# BMS_25.net
KiCad netlist of a schematic drawn in EAGLE
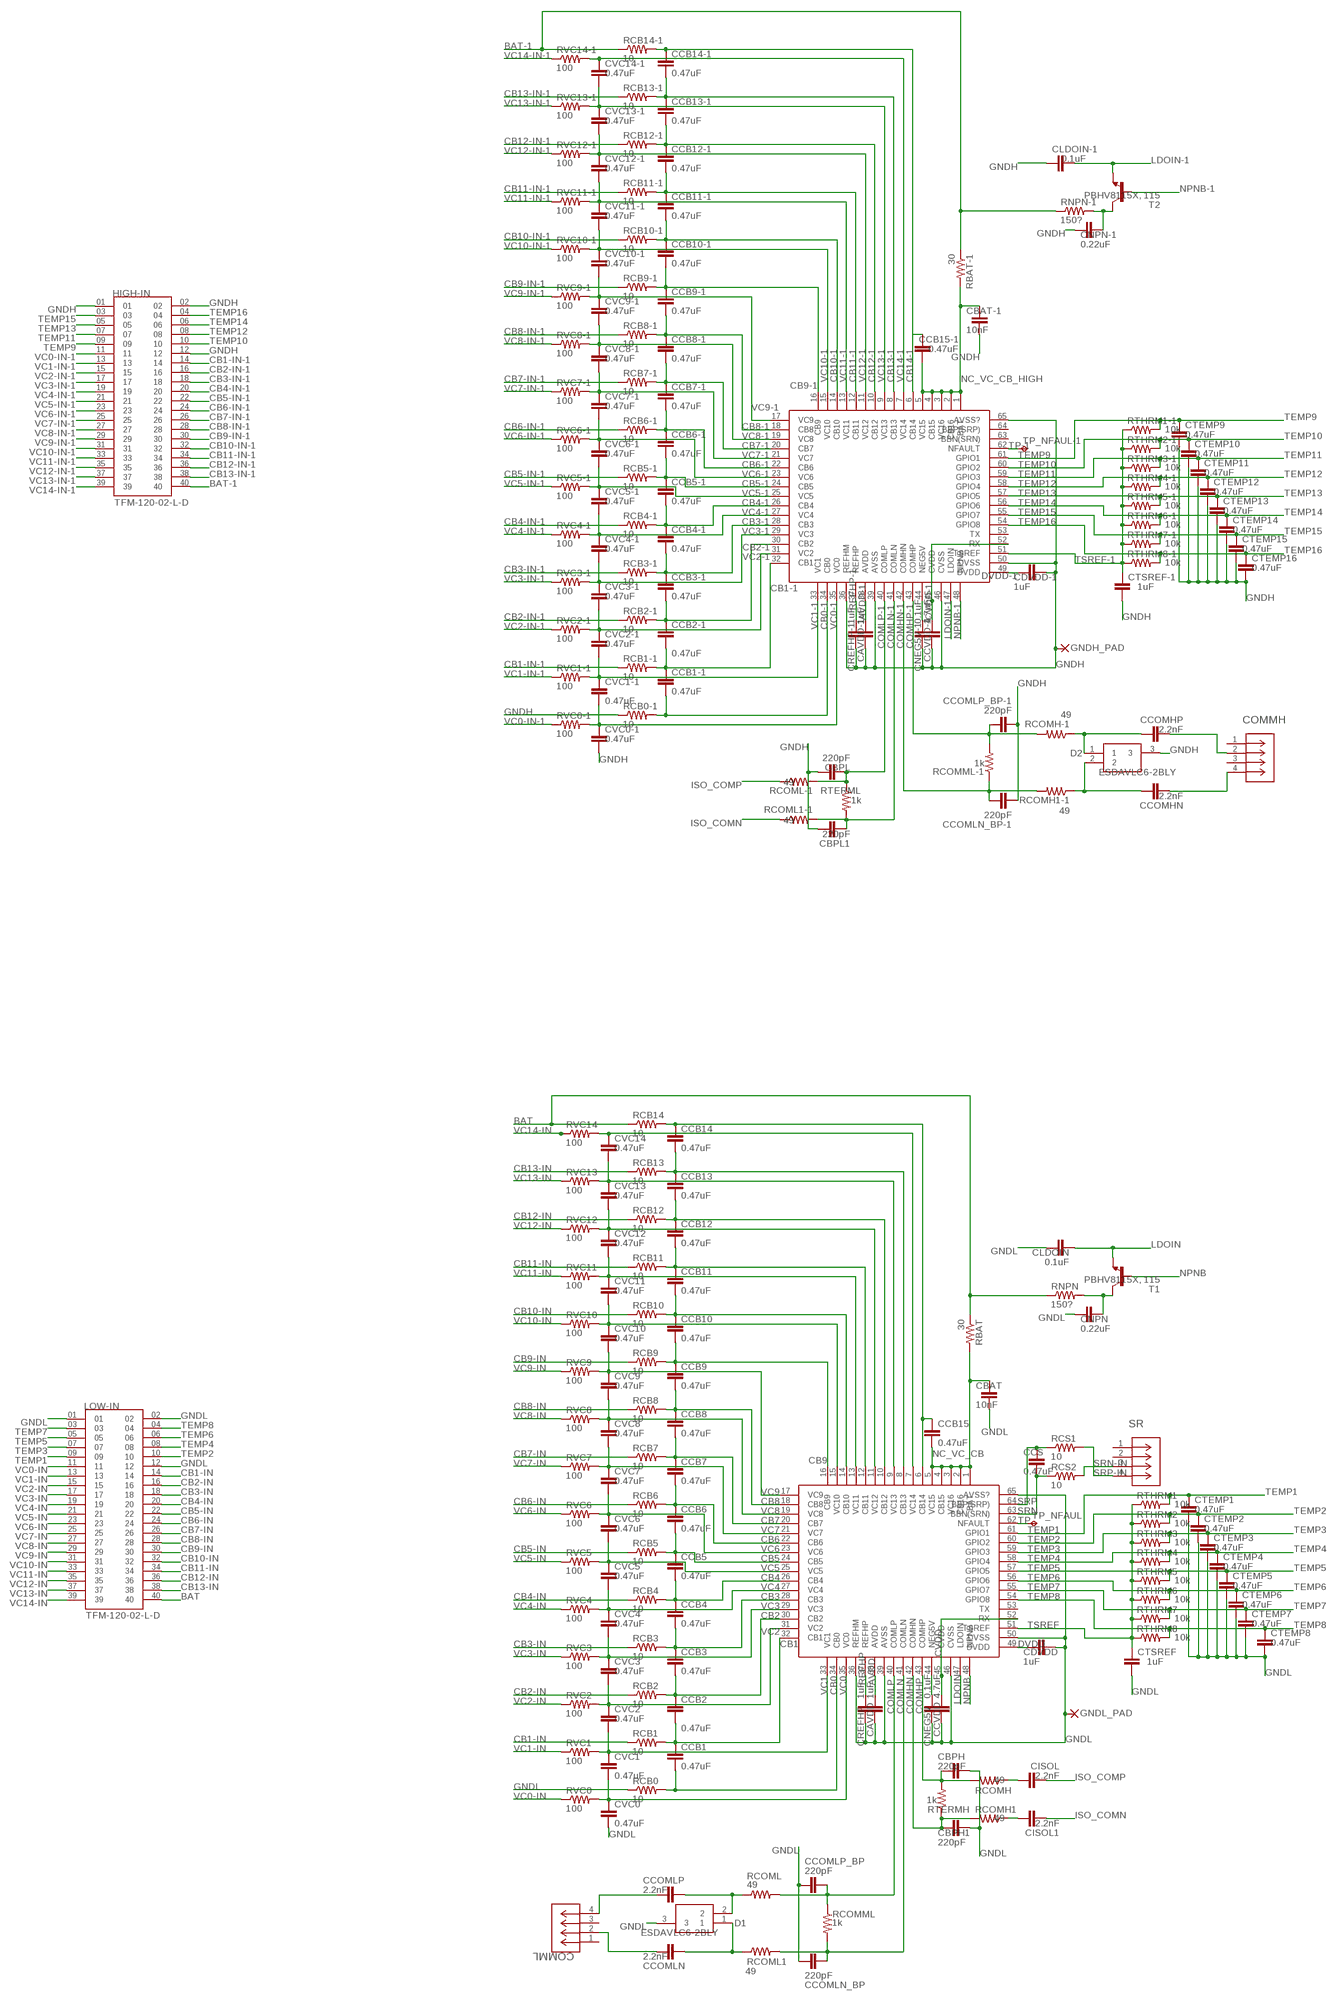
[diagram p0: schematic, sheet 1]

(export (version "E")
  (design (tool "Eeschema 10.0.6"))
  (components
    (comp (ref "CAVDD")
      (value "1uF")
      (footprint "eagle-import:C0603")
      (libsource (lib "eagle-import") (part "CAPACITORC0603"))
    )
    (comp (ref "CAVDD-1")
      (value "1uF")
      (footprint "eagle-import:C0603")
      (libsource (lib "eagle-import") (part "CAPACITORC0603"))
    )
    (comp (ref "CBAT")
      (value "10nF")
      (footprint "eagle-import:C0603")
      (libsource (lib "eagle-import") (part "CAPACITORC0603"))
    )
    (comp (ref "CBAT-1")
      (value "10nF")
      (footprint "eagle-import:C0603")
      (libsource (lib "eagle-import") (part "CAPACITORC0603"))
    )
    (comp (ref "CBPH")
      (value "220pF")
      (footprint "eagle-import:C0603")
      (libsource (lib "eagle-import") (part "CAPACITORC0603"))
    )
    (comp (ref "CBPH1")
      (value "220pF")
      (footprint "eagle-import:C0603")
      (libsource (lib "eagle-import") (part "CAPACITORC0603"))
    )
    (comp (ref "CBPL")
      (value "220pF")
      (footprint "eagle-import:C0603")
      (libsource (lib "eagle-import") (part "CAPACITORC0603"))
    )
    (comp (ref "CBPL1")
      (value "220pF")
      (footprint "eagle-import:C0603")
      (libsource (lib "eagle-import") (part "CAPACITORC0603"))
    )
    (comp (ref "CCB1")
      (value "0.47uF")
      (footprint "eagle-import:C0603")
      (libsource (lib "eagle-import") (part "CAPACITORC0603"))
    )
    (comp (ref "CCB1-1")
      (value "0.47uF")
      (footprint "eagle-import:C0603")
      (libsource (lib "eagle-import") (part "CAPACITORC0603"))
    )
    (comp (ref "CCB2")
      (value "0.47uF")
      (footprint "eagle-import:C0603")
      (libsource (lib "eagle-import") (part "CAPACITORC0603"))
    )
    (comp (ref "CCB2-1")
      (value "0.47uF")
      (footprint "eagle-import:C0603")
      (libsource (lib "eagle-import") (part "CAPACITORC0603"))
    )
    (comp (ref "CCB3")
      (value "0.47uF")
      (footprint "eagle-import:C0603")
      (libsource (lib "eagle-import") (part "CAPACITORC0603"))
    )
    (comp (ref "CCB3-1")
      (value "0.47uF")
      (footprint "eagle-import:C0603")
      (libsource (lib "eagle-import") (part "CAPACITORC0603"))
    )
    (comp (ref "CCB4")
      (value "0.47uF")
      (footprint "eagle-import:C0603")
      (libsource (lib "eagle-import") (part "CAPACITORC0603"))
    )
    (comp (ref "CCB4-1")
      (value "0.47uF")
      (footprint "eagle-import:C0603")
      (libsource (lib "eagle-import") (part "CAPACITORC0603"))
    )
    (comp (ref "CCB5")
      (value "0.47uF")
      (footprint "eagle-import:C0603")
      (libsource (lib "eagle-import") (part "CAPACITORC0603"))
    )
    (comp (ref "CCB5-1")
      (value "0.47uF")
      (footprint "eagle-import:C0603")
      (libsource (lib "eagle-import") (part "CAPACITORC0603"))
    )
    (comp (ref "CCB6")
      (value "0.47uF")
      (footprint "eagle-import:C0603")
      (libsource (lib "eagle-import") (part "CAPACITORC0603"))
    )
    (comp (ref "CCB6-1")
      (value "0.47uF")
      (footprint "eagle-import:C0603")
      (libsource (lib "eagle-import") (part "CAPACITORC0603"))
    )
    (comp (ref "CCB7")
      (value "0.47uF")
      (footprint "eagle-import:C0603")
      (libsource (lib "eagle-import") (part "CAPACITORC0603"))
    )
    (comp (ref "CCB7-1")
      (value "0.47uF")
      (footprint "eagle-import:C0603")
      (libsource (lib "eagle-import") (part "CAPACITORC0603"))
    )
    (comp (ref "CCB8")
      (value "0.47uF")
      (footprint "eagle-import:C0603")
      (libsource (lib "eagle-import") (part "CAPACITORC0603"))
    )
    (comp (ref "CCB8-1")
      (value "0.47uF")
      (footprint "eagle-import:C0603")
      (libsource (lib "eagle-import") (part "CAPACITORC0603"))
    )
    (comp (ref "CCB9")
      (value "0.47uF")
      (footprint "eagle-import:C0603")
      (libsource (lib "eagle-import") (part "CAPACITORC0603"))
    )
    (comp (ref "CCB9-1")
      (value "0.47uF")
      (footprint "eagle-import:C0603")
      (libsource (lib "eagle-import") (part "CAPACITORC0603"))
    )
    (comp (ref "CCB10")
      (value "0.47uF")
      (footprint "eagle-import:C0603")
      (libsource (lib "eagle-import") (part "CAPACITORC0603"))
    )
    (comp (ref "CCB10-1")
      (value "0.47uF")
      (footprint "eagle-import:C0603")
      (libsource (lib "eagle-import") (part "CAPACITORC0603"))
    )
    (comp (ref "CCB11")
      (value "0.47uF")
      (footprint "eagle-import:C0603")
      (libsource (lib "eagle-import") (part "CAPACITORC0603"))
    )
    (comp (ref "CCB11-1")
      (value "0.47uF")
      (footprint "eagle-import:C0603")
      (libsource (lib "eagle-import") (part "CAPACITORC0603"))
    )
    (comp (ref "CCB12")
      (value "0.47uF")
      (footprint "eagle-import:C0603")
      (libsource (lib "eagle-import") (part "CAPACITORC0603"))
    )
    (comp (ref "CCB12-1")
      (value "0.47uF")
      (footprint "eagle-import:C0603")
      (libsource (lib "eagle-import") (part "CAPACITORC0603"))
    )
    (comp (ref "CCB13")
      (value "0.47uF")
      (footprint "eagle-import:C0603")
      (libsource (lib "eagle-import") (part "CAPACITORC0603"))
    )
    (comp (ref "CCB13-1")
      (value "0.47uF")
      (footprint "eagle-import:C0603")
      (libsource (lib "eagle-import") (part "CAPACITORC0603"))
    )
    (comp (ref "CCB14")
      (value "0.47uF")
      (footprint "eagle-import:C0603")
      (libsource (lib "eagle-import") (part "CAPACITORC0603"))
    )
    (comp (ref "CCB14-1")
      (value "0.47uF")
      (footprint "eagle-import:C0603")
      (libsource (lib "eagle-import") (part "CAPACITORC0603"))
    )
    (comp (ref "CCB15")
      (value "0.47uF")
      (footprint "eagle-import:C0603")
      (libsource (lib "eagle-import") (part "CAPACITORC0603"))
    )
    (comp (ref "CCB15-1")
      (value "0.47uF")
      (footprint "eagle-import:C0603")
      (libsource (lib "eagle-import") (part "CAPACITORC0603"))
    )
    (comp (ref "CCOMHN")
      (value "2.2nF")
      (footprint "eagle-import:C0603")
      (libsource (lib "eagle-import") (part "CAPACITORC0603"))
    )
    (comp (ref "CCOMHP")
      (value "2.2nF")
      (footprint "eagle-import:C0603")
      (libsource (lib "eagle-import") (part "CAPACITORC0603"))
    )
    (comp (ref "CCOMLN")
      (value "2.2nF")
      (footprint "eagle-import:C0603")
      (libsource (lib "eagle-import") (part "CAPACITORC0603"))
    )
    (comp (ref "CCOMLN_BP")
      (value "220pF")
      (footprint "eagle-import:C0603")
      (libsource (lib "eagle-import") (part "CAPACITORC0603"))
    )
    (comp (ref "CCOMLN_BP-1")
      (value "220pF")
      (footprint "eagle-import:C0603")
      (libsource (lib "eagle-import") (part "CAPACITORC0603"))
    )
    (comp (ref "CCOMLP")
      (value "2.2nF")
      (footprint "eagle-import:C0603")
      (libsource (lib "eagle-import") (part "CAPACITORC0603"))
    )
    (comp (ref "CCOMLP_BP")
      (value "220pF")
      (footprint "eagle-import:C0603")
      (libsource (lib "eagle-import") (part "CAPACITORC0603"))
    )
    (comp (ref "CCOMLP_BP-1")
      (value "220pF")
      (footprint "eagle-import:C0603")
      (libsource (lib "eagle-import") (part "CAPACITORC0603"))
    )
    (comp (ref "CCS")
      (value "0.47uF")
      (footprint "eagle-import:C0603")
      (libsource (lib "eagle-import") (part "CAPACITORC0603"))
    )
    (comp (ref "CCVDD")
      (value "4.7uF")
      (footprint "eagle-import:C0603")
      (libsource (lib "eagle-import") (part "CAPACITORC0603"))
    )
    (comp (ref "CCVDD-1")
      (value "4.7uF")
      (footprint "eagle-import:C0603")
      (libsource (lib "eagle-import") (part "CAPACITORC0603"))
    )
    (comp (ref "CDVDD")
      (value "1uF")
      (footprint "eagle-import:C0603")
      (libsource (lib "eagle-import") (part "CAPACITORC0603"))
    )
    (comp (ref "CDVDD-1")
      (value "1uF")
      (footprint "eagle-import:C0603")
      (libsource (lib "eagle-import") (part "CAPACITORC0603"))
    )
    (comp (ref "CISOL")
      (value "2.2nF")
      (footprint "eagle-import:C0603")
      (libsource (lib "eagle-import") (part "CAPACITORC0603"))
    )
    (comp (ref "CISOL1")
      (value "2.2nF")
      (footprint "eagle-import:C0603")
      (libsource (lib "eagle-import") (part "CAPACITORC0603"))
    )
    (comp (ref "CLDOIN")
      (value "0.1uF")
      (footprint "eagle-import:C0603")
      (libsource (lib "eagle-import") (part "CAPACITORC0603"))
    )
    (comp (ref "CLDOIN-1")
      (value "0.1uF")
      (footprint "eagle-import:C0603")
      (libsource (lib "eagle-import") (part "CAPACITORC0603"))
    )
    (comp (ref "CNEG5V")
      (value "0.1uF")
      (footprint "eagle-import:C0603")
      (libsource (lib "eagle-import") (part "CAPACITORC0603"))
    )
    (comp (ref "CNEG5V-1")
      (value "0.1uF")
      (footprint "eagle-import:C0603")
      (libsource (lib "eagle-import") (part "CAPACITORC0603"))
    )
    (comp (ref "CNPN")
      (value "0.22uF")
      (footprint "eagle-import:C0603")
      (libsource (lib "eagle-import") (part "CAPACITORC0603"))
    )
    (comp (ref "CNPN-1")
      (value "0.22uF")
      (footprint "eagle-import:C0603")
      (libsource (lib "eagle-import") (part "CAPACITORC0603"))
    )
    (comp (ref "COMMH")
      (value "DF11-4DP-2DSA(24)")
      (footprint "eagle-import:CON4_2X2_UF_DF11_HIR")
      (fields (field (name "COPYRIGHT") "Copyright (C) 2023 Ultra Librarian. All rights reserved."))
      (libsource (lib "eagle-import") (part "DF11-4DP-2DSA(24)"))
    )
    (comp (ref "COMML")
      (value "DF11-4DP-2DSA(24)")
      (footprint "eagle-import:CON4_2X2_UF_DF11_HIR")
      (fields (field (name "COPYRIGHT") "Copyright (C) 2023 Ultra Librarian. All rights reserved."))
      (libsource (lib "eagle-import") (part "DF11-4DP-2DSA(24)"))
    )
    (comp (ref "CREFHP")
      (value "1uF")
      (footprint "eagle-import:C0603")
      (libsource (lib "eagle-import") (part "CAPACITORC0603"))
    )
    (comp (ref "CREFHP-1")
      (value "1uF")
      (footprint "eagle-import:C0603")
      (libsource (lib "eagle-import") (part "CAPACITORC0603"))
    )
    (comp (ref "CTEMP1")
      (value "0.47uF")
      (footprint "eagle-import:C0603")
      (libsource (lib "eagle-import") (part "CAPACITORC0603"))
    )
    (comp (ref "CTEMP2")
      (value "0.47uF")
      (footprint "eagle-import:C0603")
      (libsource (lib "eagle-import") (part "CAPACITORC0603"))
    )
    (comp (ref "CTEMP3")
      (value "0.47uF")
      (footprint "eagle-import:C0603")
      (libsource (lib "eagle-import") (part "CAPACITORC0603"))
    )
    (comp (ref "CTEMP4")
      (value "0.47uF")
      (footprint "eagle-import:C0603")
      (libsource (lib "eagle-import") (part "CAPACITORC0603"))
    )
    (comp (ref "CTEMP5")
      (value "0.47uF")
      (footprint "eagle-import:C0603")
      (libsource (lib "eagle-import") (part "CAPACITORC0603"))
    )
    (comp (ref "CTEMP6")
      (value "0.47uF")
      (footprint "eagle-import:C0603")
      (libsource (lib "eagle-import") (part "CAPACITORC0603"))
    )
    (comp (ref "CTEMP7")
      (value "0.47uF")
      (footprint "eagle-import:C0603")
      (libsource (lib "eagle-import") (part "CAPACITORC0603"))
    )
    (comp (ref "CTEMP8")
      (value "0.47uF")
      (footprint "eagle-import:C0603")
      (libsource (lib "eagle-import") (part "CAPACITORC0603"))
    )
    (comp (ref "CTEMP9")
      (value "0.47uF")
      (footprint "eagle-import:C0603")
      (libsource (lib "eagle-import") (part "CAPACITORC0603"))
    )
    (comp (ref "CTEMP10")
      (value "0.47uF")
      (footprint "eagle-import:C0603")
      (libsource (lib "eagle-import") (part "CAPACITORC0603"))
    )
    (comp (ref "CTEMP11")
      (value "0.47uF")
      (footprint "eagle-import:C0603")
      (libsource (lib "eagle-import") (part "CAPACITORC0603"))
    )
    (comp (ref "CTEMP12")
      (value "0.47uF")
      (footprint "eagle-import:C0603")
      (libsource (lib "eagle-import") (part "CAPACITORC0603"))
    )
    (comp (ref "CTEMP13")
      (value "0.47uF")
      (footprint "eagle-import:C0603")
      (libsource (lib "eagle-import") (part "CAPACITORC0603"))
    )
    (comp (ref "CTEMP14")
      (value "0.47uF")
      (footprint "eagle-import:C0603")
      (libsource (lib "eagle-import") (part "CAPACITORC0603"))
    )
    (comp (ref "CTEMP15")
      (value "0.47uF")
      (footprint "eagle-import:C0603")
      (libsource (lib "eagle-import") (part "CAPACITORC0603"))
    )
    (comp (ref "CTEMP16")
      (value "0.47uF")
      (footprint "eagle-import:C0603")
      (libsource (lib "eagle-import") (part "CAPACITORC0603"))
    )
    (comp (ref "CTSREF")
      (value "1uF")
      (footprint "eagle-import:C0603")
      (libsource (lib "eagle-import") (part "CAPACITORC0603"))
    )
    (comp (ref "CTSREF-1")
      (value "1uF")
      (footprint "eagle-import:C0603")
      (libsource (lib "eagle-import") (part "CAPACITORC0603"))
    )
    (comp (ref "CVC0")
      (value "0.47uF")
      (footprint "eagle-import:C0603")
      (libsource (lib "eagle-import") (part "CAPACITORC0603"))
    )
    (comp (ref "CVC0-1")
      (value "0.47uF")
      (footprint "eagle-import:C0603")
      (libsource (lib "eagle-import") (part "CAPACITORC0603"))
    )
    (comp (ref "CVC1")
      (value "0.47uF")
      (footprint "eagle-import:C0603")
      (libsource (lib "eagle-import") (part "CAPACITORC0603"))
    )
    (comp (ref "CVC1-1")
      (value "0.47uF")
      (footprint "eagle-import:C0603")
      (libsource (lib "eagle-import") (part "CAPACITORC0603"))
    )
    (comp (ref "CVC2")
      (value "0.47uF")
      (footprint "eagle-import:C0603")
      (libsource (lib "eagle-import") (part "CAPACITORC0603"))
    )
    (comp (ref "CVC2-1")
      (value "0.47uF")
      (footprint "eagle-import:C0603")
      (libsource (lib "eagle-import") (part "CAPACITORC0603"))
    )
    (comp (ref "CVC3")
      (value "0.47uF")
      (footprint "eagle-import:C0603")
      (libsource (lib "eagle-import") (part "CAPACITORC0603"))
    )
    (comp (ref "CVC3-1")
      (value "0.47uF")
      (footprint "eagle-import:C0603")
      (libsource (lib "eagle-import") (part "CAPACITORC0603"))
    )
    (comp (ref "CVC4")
      (value "0.47uF")
      (footprint "eagle-import:C0603")
      (libsource (lib "eagle-import") (part "CAPACITORC0603"))
    )
    (comp (ref "CVC4-1")
      (value "0.47uF")
      (footprint "eagle-import:C0603")
      (libsource (lib "eagle-import") (part "CAPACITORC0603"))
    )
    (comp (ref "CVC5")
      (value "0.47uF")
      (footprint "eagle-import:C0603")
      (libsource (lib "eagle-import") (part "CAPACITORC0603"))
    )
    (comp (ref "CVC5-1")
      (value "0.47uF")
      (footprint "eagle-import:C0603")
      (libsource (lib "eagle-import") (part "CAPACITORC0603"))
    )
    (comp (ref "CVC6")
      (value "0.47uF")
      (footprint "eagle-import:C0603")
      (libsource (lib "eagle-import") (part "CAPACITORC0603"))
    )
    (comp (ref "CVC6-1")
      (value "0.47uF")
      (footprint "eagle-import:C0603")
      (libsource (lib "eagle-import") (part "CAPACITORC0603"))
    )
    (comp (ref "CVC7")
      (value "0.47uF")
      (footprint "eagle-import:C0603")
      (libsource (lib "eagle-import") (part "CAPACITORC0603"))
    )
    (comp (ref "CVC7-1")
      (value "0.47uF")
      (footprint "eagle-import:C0603")
      (libsource (lib "eagle-import") (part "CAPACITORC0603"))
    )
    (comp (ref "CVC8")
      (value "0.47uF")
      (footprint "eagle-import:C0603")
      (libsource (lib "eagle-import") (part "CAPACITORC0603"))
    )
    (comp (ref "CVC8-1")
      (value "0.47uF")
      (footprint "eagle-import:C0603")
      (libsource (lib "eagle-import") (part "CAPACITORC0603"))
    )
    (comp (ref "CVC9")
      (value "0.47uF")
      (footprint "eagle-import:C0603")
      (libsource (lib "eagle-import") (part "CAPACITORC0603"))
    )
    (comp (ref "CVC9-1")
      (value "0.47uF")
      (footprint "eagle-import:C0603")
      (libsource (lib "eagle-import") (part "CAPACITORC0603"))
    )
    (comp (ref "CVC10")
      (value "0.47uF")
      (footprint "eagle-import:C0603")
      (libsource (lib "eagle-import") (part "CAPACITORC0603"))
    )
    (comp (ref "CVC10-1")
      (value "0.47uF")
      (footprint "eagle-import:C0603")
      (libsource (lib "eagle-import") (part "CAPACITORC0603"))
    )
    (comp (ref "CVC11")
      (value "0.47uF")
      (footprint "eagle-import:C0603")
      (libsource (lib "eagle-import") (part "CAPACITORC0603"))
    )
    (comp (ref "CVC11-1")
      (value "0.47uF")
      (footprint "eagle-import:C0603")
      (libsource (lib "eagle-import") (part "CAPACITORC0603"))
    )
    (comp (ref "CVC12")
      (value "0.47uF")
      (footprint "eagle-import:C0603")
      (libsource (lib "eagle-import") (part "CAPACITORC0603"))
    )
    (comp (ref "CVC12-1")
      (value "0.47uF")
      (footprint "eagle-import:C0603")
      (libsource (lib "eagle-import") (part "CAPACITORC0603"))
    )
    (comp (ref "CVC13")
      (value "0.47uF")
      (footprint "eagle-import:C0603")
      (libsource (lib "eagle-import") (part "CAPACITORC0603"))
    )
    (comp (ref "CVC13-1")
      (value "0.47uF")
      (footprint "eagle-import:C0603")
      (libsource (lib "eagle-import") (part "CAPACITORC0603"))
    )
    (comp (ref "CVC14")
      (value "0.47uF")
      (footprint "eagle-import:C0603")
      (libsource (lib "eagle-import") (part "CAPACITORC0603"))
    )
    (comp (ref "CVC14-1")
      (value "0.47uF")
      (footprint "eagle-import:C0603")
      (libsource (lib "eagle-import") (part "CAPACITORC0603"))
    )
    (comp (ref "D1")
      (value "ESDAVLC6-2BLY")
      (footprint "eagle-import:SOT95P255X150-3N")
      (fields (field (name "MOUSER_PART_NUMBER") "511-ESDAVLC6-2BLY"))
      (libsource (lib "eagle-import") (part "ESDAVLC6-2BLY"))
    )
    (comp (ref "D2")
      (value "ESDAVLC6-2BLY")
      (footprint "eagle-import:SOT95P255X150-3N")
      (fields (field (name "MOUSER_PART_NUMBER") "511-ESDAVLC6-2BLY"))
      (libsource (lib "eagle-import") (part "ESDAVLC6-2BLY"))
    )
    (comp (ref "GNDH_PAD")
      (value "SMD2")
      (footprint "eagle-import:SMD1,27-2,54")
      (libsource (lib "eagle-import") (part "SMD2"))
    )
    (comp (ref "GNDL_PAD")
      (value "SMD2")
      (footprint "eagle-import:SMD1,27-2,54")
      (libsource (lib "eagle-import") (part "SMD2"))
    )
    (comp (ref "HIGH-IN")
      (value "TFM-120-02-L-D")
      (footprint "eagle-import:SAMTEC_TFM-120-02-L-D")
      (fields (field (name "MANUFACTURER") "Samtec"))
      (libsource (lib "eagle-import") (part "TFM-120-02-L-D"))
    )
    (comp (ref "IC1")
      (value "PBQ79656PAPTQ1")
      (footprint "eagle-import:QFP50P1200X1200X120-65N")
      (libsource (lib "eagle-import") (part "PBQ79656PAPTQ1"))
    )
    (comp (ref "IC2")
      (value "PBQ79656PAPTQ1")
      (footprint "eagle-import:QFP50P1200X1200X120-65N")
      (libsource (lib "eagle-import") (part "PBQ79656PAPTQ1"))
    )
    (comp (ref "LOW-IN")
      (value "TFM-120-02-L-D")
      (footprint "eagle-import:SAMTEC_TFM-120-02-L-D")
      (fields (field (name "MANUFACTURER") "Samtec"))
      (libsource (lib "eagle-import") (part "TFM-120-02-L-D"))
    )
    (comp (ref "RBAT")
      (value "30")
      (footprint "eagle-import:R0603")
      (libsource (lib "eagle-import") (part "RESISTORR0603"))
    )
    (comp (ref "RBAT-1")
      (value "30")
      (footprint "eagle-import:R0603")
      (libsource (lib "eagle-import") (part "RESISTORR0603"))
    )
    (comp (ref "RCB0")
      (value "10")
      (footprint "eagle-import:R2010")
      (libsource (lib "eagle-import") (part "R-US_R2010"))
    )
    (comp (ref "RCB0-1")
      (value "10")
      (footprint "eagle-import:R2010")
      (libsource (lib "eagle-import") (part "R-US_R2010"))
    )
    (comp (ref "RCB1")
      (value "10")
      (footprint "eagle-import:R2010")
      (libsource (lib "eagle-import") (part "R-US_R2010"))
    )
    (comp (ref "RCB1-1")
      (value "10")
      (footprint "eagle-import:R2010")
      (libsource (lib "eagle-import") (part "R-US_R2010"))
    )
    (comp (ref "RCB2")
      (value "10")
      (footprint "eagle-import:R2010")
      (libsource (lib "eagle-import") (part "R-US_R2010"))
    )
    (comp (ref "RCB2-1")
      (value "10")
      (footprint "eagle-import:R2010")
      (libsource (lib "eagle-import") (part "R-US_R2010"))
    )
    (comp (ref "RCB3")
      (value "10")
      (footprint "eagle-import:R2010")
      (libsource (lib "eagle-import") (part "R-US_R2010"))
    )
    (comp (ref "RCB3-1")
      (value "10")
      (footprint "eagle-import:R2010")
      (libsource (lib "eagle-import") (part "R-US_R2010"))
    )
    (comp (ref "RCB4")
      (value "10")
      (footprint "eagle-import:R2010")
      (libsource (lib "eagle-import") (part "R-US_R2010"))
    )
    (comp (ref "RCB4-1")
      (value "10")
      (footprint "eagle-import:R2010")
      (libsource (lib "eagle-import") (part "R-US_R2010"))
    )
    (comp (ref "RCB5")
      (value "10")
      (footprint "eagle-import:R2010")
      (libsource (lib "eagle-import") (part "R-US_R2010"))
    )
    (comp (ref "RCB5-1")
      (value "10")
      (footprint "eagle-import:R2010")
      (libsource (lib "eagle-import") (part "R-US_R2010"))
    )
    (comp (ref "RCB6")
      (value "10")
      (footprint "eagle-import:R2010")
      (libsource (lib "eagle-import") (part "R-US_R2010"))
    )
    (comp (ref "RCB6-1")
      (value "10")
      (footprint "eagle-import:R2010")
      (libsource (lib "eagle-import") (part "R-US_R2010"))
    )
    (comp (ref "RCB7")
      (value "10")
      (footprint "eagle-import:R2010")
      (libsource (lib "eagle-import") (part "R-US_R2010"))
    )
    (comp (ref "RCB7-1")
      (value "10")
      (footprint "eagle-import:R2010")
      (libsource (lib "eagle-import") (part "R-US_R2010"))
    )
    (comp (ref "RCB8")
      (value "10")
      (footprint "eagle-import:R2010")
      (libsource (lib "eagle-import") (part "R-US_R2010"))
    )
    (comp (ref "RCB8-1")
      (value "10")
      (footprint "eagle-import:R2010")
      (libsource (lib "eagle-import") (part "R-US_R2010"))
    )
    (comp (ref "RCB9")
      (value "10")
      (footprint "eagle-import:R2010")
      (libsource (lib "eagle-import") (part "R-US_R2010"))
    )
    (comp (ref "RCB9-1")
      (value "10")
      (footprint "eagle-import:R2010")
      (libsource (lib "eagle-import") (part "R-US_R2010"))
    )
    (comp (ref "RCB10")
      (value "10")
      (footprint "eagle-import:R2010")
      (libsource (lib "eagle-import") (part "R-US_R2010"))
    )
    (comp (ref "RCB10-1")
      (value "10")
      (footprint "eagle-import:R2010")
      (libsource (lib "eagle-import") (part "R-US_R2010"))
    )
    (comp (ref "RCB11")
      (value "10")
      (footprint "eagle-import:R2010")
      (libsource (lib "eagle-import") (part "R-US_R2010"))
    )
    (comp (ref "RCB11-1")
      (value "10")
      (footprint "eagle-import:R2010")
      (libsource (lib "eagle-import") (part "R-US_R2010"))
    )
    (comp (ref "RCB12")
      (value "10")
      (footprint "eagle-import:R2010")
      (libsource (lib "eagle-import") (part "R-US_R2010"))
    )
    (comp (ref "RCB12-1")
      (value "10")
      (footprint "eagle-import:R2010")
      (libsource (lib "eagle-import") (part "R-US_R2010"))
    )
    (comp (ref "RCB13")
      (value "10")
      (footprint "eagle-import:R2010")
      (libsource (lib "eagle-import") (part "R-US_R2010"))
    )
    (comp (ref "RCB13-1")
      (value "10")
      (footprint "eagle-import:R2010")
      (libsource (lib "eagle-import") (part "R-US_R2010"))
    )
    (comp (ref "RCB14")
      (value "10")
      (footprint "eagle-import:R2010")
      (libsource (lib "eagle-import") (part "R-US_R2010"))
    )
    (comp (ref "RCB14-1")
      (value "10")
      (footprint "eagle-import:R2010")
      (libsource (lib "eagle-import") (part "R-US_R2010"))
    )
    (comp (ref "RCOMH")
      (value "49")
      (footprint "eagle-import:R0603")
      (libsource (lib "eagle-import") (part "RESISTORR0603"))
    )
    (comp (ref "RCOMH-1")
      (value "49")
      (footprint "eagle-import:R0603")
      (libsource (lib "eagle-import") (part "RESISTORR0603"))
    )
    (comp (ref "RCOMH1")
      (value "49")
      (footprint "eagle-import:R0603")
      (libsource (lib "eagle-import") (part "RESISTORR0603"))
    )
    (comp (ref "RCOMH1-1")
      (value "49")
      (footprint "eagle-import:R0603")
      (libsource (lib "eagle-import") (part "RESISTORR0603"))
    )
    (comp (ref "RCOML")
      (value "49")
      (footprint "eagle-import:R0603")
      (libsource (lib "eagle-import") (part "RESISTORR0603"))
    )
    (comp (ref "RCOML-1")
      (value "49")
      (footprint "eagle-import:R0603")
      (libsource (lib "eagle-import") (part "RESISTORR0603"))
    )
    (comp (ref "RCOML1")
      (value "49")
      (footprint "eagle-import:R0603")
      (libsource (lib "eagle-import") (part "RESISTORR0603"))
    )
    (comp (ref "RCOML1-1")
      (value "49")
      (footprint "eagle-import:R0603")
      (libsource (lib "eagle-import") (part "RESISTORR0603"))
    )
    (comp (ref "RCOMML")
      (value "1k")
      (footprint "eagle-import:R0603")
      (libsource (lib "eagle-import") (part "RESISTORR0603"))
    )
    (comp (ref "RCOMML-1")
      (value "1k")
      (footprint "eagle-import:R0603")
      (libsource (lib "eagle-import") (part "RESISTORR0603"))
    )
    (comp (ref "RCS1")
      (value "10")
      (footprint "eagle-import:R0603")
      (libsource (lib "eagle-import") (part "RESISTORR0603"))
    )
    (comp (ref "RCS2")
      (value "10")
      (footprint "eagle-import:R0603")
      (libsource (lib "eagle-import") (part "RESISTORR0603"))
    )
    (comp (ref "RNPN")
      (value "150?")
      (footprint "eagle-import:R2512W")
      (libsource (lib "eagle-import") (part "R-US_R2512W"))
    )
    (comp (ref "RNPN-1")
      (value "150?")
      (footprint "eagle-import:R2512W")
      (libsource (lib "eagle-import") (part "R-US_R2512W"))
    )
    (comp (ref "RTERMH")
      (value "1k")
      (footprint "eagle-import:R0603")
      (libsource (lib "eagle-import") (part "RESISTORR0603"))
    )
    (comp (ref "RTERML")
      (value "1k")
      (footprint "eagle-import:R0603")
      (libsource (lib "eagle-import") (part "RESISTORR0603"))
    )
    (comp (ref "RTHRM1")
      (value "10k")
      (footprint "eagle-import:R0603")
      (libsource (lib "eagle-import") (part "RESISTORR0603"))
    )
    (comp (ref "RTHRM1-1")
      (value "10k")
      (footprint "eagle-import:R0603")
      (libsource (lib "eagle-import") (part "RESISTORR0603"))
    )
    (comp (ref "RTHRM2")
      (value "10k")
      (footprint "eagle-import:R0603")
      (libsource (lib "eagle-import") (part "RESISTORR0603"))
    )
    (comp (ref "RTHRM2-1")
      (value "10k")
      (footprint "eagle-import:R0603")
      (libsource (lib "eagle-import") (part "RESISTORR0603"))
    )
    (comp (ref "RTHRM3")
      (value "10k")
      (footprint "eagle-import:R0603")
      (libsource (lib "eagle-import") (part "RESISTORR0603"))
    )
    (comp (ref "RTHRM3-1")
      (value "10k")
      (footprint "eagle-import:R0603")
      (libsource (lib "eagle-import") (part "RESISTORR0603"))
    )
    (comp (ref "RTHRM4")
      (value "10k")
      (footprint "eagle-import:R0603")
      (libsource (lib "eagle-import") (part "RESISTORR0603"))
    )
    (comp (ref "RTHRM4-1")
      (value "10k")
      (footprint "eagle-import:R0603")
      (libsource (lib "eagle-import") (part "RESISTORR0603"))
    )
    (comp (ref "RTHRM5")
      (value "10k")
      (footprint "eagle-import:R0603")
      (libsource (lib "eagle-import") (part "RESISTORR0603"))
    )
    (comp (ref "RTHRM5-1")
      (value "10k")
      (footprint "eagle-import:R0603")
      (libsource (lib "eagle-import") (part "RESISTORR0603"))
    )
    (comp (ref "RTHRM6")
      (value "10k")
      (footprint "eagle-import:R0603")
      (libsource (lib "eagle-import") (part "RESISTORR0603"))
    )
    (comp (ref "RTHRM6-1")
      (value "10k")
      (footprint "eagle-import:R0603")
      (libsource (lib "eagle-import") (part "RESISTORR0603"))
    )
    (comp (ref "RTHRM7")
      (value "10k")
      (footprint "eagle-import:R0603")
      (libsource (lib "eagle-import") (part "RESISTORR0603"))
    )
    (comp (ref "RTHRM7-1")
      (value "10k")
      (footprint "eagle-import:R0603")
      (libsource (lib "eagle-import") (part "RESISTORR0603"))
    )
    (comp (ref "RTHRM8")
      (value "10k")
      (footprint "eagle-import:R0603")
      (libsource (lib "eagle-import") (part "RESISTORR0603"))
    )
    (comp (ref "RTHRM8-1")
      (value "10k")
      (footprint "eagle-import:R0603")
      (libsource (lib "eagle-import") (part "RESISTORR0603"))
    )
    (comp (ref "RVC0")
      (value "100")
      (footprint "eagle-import:R0603")
      (libsource (lib "eagle-import") (part "RESISTORR0603"))
    )
    (comp (ref "RVC0-1")
      (value "100")
      (footprint "eagle-import:R0603")
      (libsource (lib "eagle-import") (part "RESISTORR0603"))
    )
    (comp (ref "RVC1")
      (value "100")
      (footprint "eagle-import:R0603")
      (libsource (lib "eagle-import") (part "RESISTORR0603"))
    )
    (comp (ref "RVC1-1")
      (value "100")
      (footprint "eagle-import:R0603")
      (libsource (lib "eagle-import") (part "RESISTORR0603"))
    )
    (comp (ref "RVC2")
      (value "100")
      (footprint "eagle-import:R0603")
      (libsource (lib "eagle-import") (part "RESISTORR0603"))
    )
    (comp (ref "RVC2-1")
      (value "100")
      (footprint "eagle-import:R0603")
      (libsource (lib "eagle-import") (part "RESISTORR0603"))
    )
    (comp (ref "RVC3")
      (value "100")
      (footprint "eagle-import:R0603")
      (libsource (lib "eagle-import") (part "RESISTORR0603"))
    )
    (comp (ref "RVC3-1")
      (value "100")
      (footprint "eagle-import:R0603")
      (libsource (lib "eagle-import") (part "RESISTORR0603"))
    )
    (comp (ref "RVC4")
      (value "100")
      (footprint "eagle-import:R0603")
      (libsource (lib "eagle-import") (part "RESISTORR0603"))
    )
    (comp (ref "RVC4-1")
      (value "100")
      (footprint "eagle-import:R0603")
      (libsource (lib "eagle-import") (part "RESISTORR0603"))
    )
    (comp (ref "RVC5")
      (value "100")
      (footprint "eagle-import:R0603")
      (libsource (lib "eagle-import") (part "RESISTORR0603"))
    )
    (comp (ref "RVC5-1")
      (value "100")
      (footprint "eagle-import:R0603")
      (libsource (lib "eagle-import") (part "RESISTORR0603"))
    )
    (comp (ref "RVC6")
      (value "100")
      (footprint "eagle-import:R0603")
      (libsource (lib "eagle-import") (part "RESISTORR0603"))
    )
    (comp (ref "RVC6-1")
      (value "100")
      (footprint "eagle-import:R0603")
      (libsource (lib "eagle-import") (part "RESISTORR0603"))
    )
    (comp (ref "RVC7")
      (value "100")
      (footprint "eagle-import:R0603")
      (libsource (lib "eagle-import") (part "RESISTORR0603"))
    )
    (comp (ref "RVC7-1")
      (value "100")
      (footprint "eagle-import:R0603")
      (libsource (lib "eagle-import") (part "RESISTORR0603"))
    )
    (comp (ref "RVC8")
      (value "100")
      (footprint "eagle-import:R0603")
      (libsource (lib "eagle-import") (part "RESISTORR0603"))
    )
    (comp (ref "RVC8-1")
      (value "100")
      (footprint "eagle-import:R0603")
      (libsource (lib "eagle-import") (part "RESISTORR0603"))
    )
    (comp (ref "RVC9")
      (value "100")
      (footprint "eagle-import:R0603")
      (libsource (lib "eagle-import") (part "RESISTORR0603"))
    )
    (comp (ref "RVC9-1")
      (value "100")
      (footprint "eagle-import:R0603")
      (libsource (lib "eagle-import") (part "RESISTORR0603"))
    )
    (comp (ref "RVC10")
      (value "100")
      (footprint "eagle-import:R0603")
      (libsource (lib "eagle-import") (part "RESISTORR0603"))
    )
    (comp (ref "RVC10-1")
      (value "100")
      (footprint "eagle-import:R0603")
      (libsource (lib "eagle-import") (part "RESISTORR0603"))
    )
    (comp (ref "RVC11")
      (value "100")
      (footprint "eagle-import:R0603")
      (libsource (lib "eagle-import") (part "RESISTORR0603"))
    )
    (comp (ref "RVC11-1")
      (value "100")
      (footprint "eagle-import:R0603")
      (libsource (lib "eagle-import") (part "RESISTORR0603"))
    )
    (comp (ref "RVC12")
      (value "100")
      (footprint "eagle-import:R0603")
      (libsource (lib "eagle-import") (part "RESISTORR0603"))
    )
    (comp (ref "RVC12-1")
      (value "100")
      (footprint "eagle-import:R0603")
      (libsource (lib "eagle-import") (part "RESISTORR0603"))
    )
    (comp (ref "RVC13")
      (value "100")
      (footprint "eagle-import:R0603")
      (libsource (lib "eagle-import") (part "RESISTORR0603"))
    )
    (comp (ref "RVC13-1")
      (value "100")
      (footprint "eagle-import:R0603")
      (libsource (lib "eagle-import") (part "RESISTORR0603"))
    )
    (comp (ref "RVC14")
      (value "100")
      (footprint "eagle-import:R0603")
      (libsource (lib "eagle-import") (part "RESISTORR0603"))
    )
    (comp (ref "RVC14-1")
      (value "100")
      (footprint "eagle-import:R0603")
      (libsource (lib "eagle-import") (part "RESISTORR0603"))
    )
    (comp (ref "SR")
      (value "DF11-4DP-2DSA(24)")
      (footprint "eagle-import:CON4_2X2_UF_DF11_HIR")
      (fields (field (name "COPYRIGHT") "Copyright (C) 2023 Ultra Librarian. All rights reserved."))
      (libsource (lib "eagle-import") (part "DF11-4DP-2DSA(24)"))
    )
    (comp (ref "T1")
      (value "PBHV8115X, 115")
      (footprint "eagle-import:SOT89-BCE")
      (libsource (lib "eagle-import") (part "-NPN-SOT89-BCEBC868"))
    )
    (comp (ref "T2")
      (value "PBHV8115X, 115")
      (footprint "eagle-import:SOT89-BCE")
      (libsource (lib "eagle-import") (part "-NPN-SOT89-BCEBC868"))
    )
    (comp (ref "TP_NFAUL")
      (value "TPB2,54")
      (footprint "eagle-import:B2,54")
      (libsource (lib "eagle-import") (part "TPB2,54"))
    )
    (comp (ref "TP_NFAUL-1")
      (value "TPB2,54")
      (footprint "eagle-import:B2,54")
      (libsource (lib "eagle-import") (part "TPB2,54"))
    )
  )
  (nets
    (net (code "1") (name "/AVDD") (class "Default")
      (node (ref "CAVDD") (pin "1") (pinfunction "1_1") (pintype "passive"))
      (node (ref "IC2") (pin "38") (pinfunction "AVDD_38") (pintype "bidirectional"))
    )
    (net (code "2") (name "/AVDD-1") (class "Default")
      (node (ref "CAVDD-1") (pin "1") (pinfunction "1_1") (pintype "passive"))
      (node (ref "IC1") (pin "38") (pinfunction "AVDD_38") (pintype "bidirectional"))
    )
    (net (code "3") (name "/BAT") (class "Default")
      (node (ref "LOW-IN") (pin "40") (pinfunction "40_40") (pintype "passive"))
      (node (ref "RBAT") (pin "1") (pinfunction "1_1") (pintype "passive"))
      (node (ref "RCB14") (pin "1") (pinfunction "1_1") (pintype "passive"))
      (node (ref "RNPN") (pin "1") (pinfunction "1_1") (pintype "passive"))
    )
    (net (code "4") (name "/BAT-1") (class "Default")
      (node (ref "HIGH-IN") (pin "40") (pinfunction "40_40") (pintype "passive"))
      (node (ref "RBAT-1") (pin "1") (pinfunction "1_1") (pintype "passive"))
      (node (ref "RCB14-1") (pin "1") (pinfunction "1_1") (pintype "passive"))
      (node (ref "RNPN-1") (pin "1") (pinfunction "1_1") (pintype "passive"))
    )
    (net (code "5") (name "/CB0") (class "Default")
      (node (ref "CCB1") (pin "2") (pinfunction "2_2") (pintype "passive"))
      (node (ref "IC2") (pin "34") (pinfunction "CB0_34") (pintype "bidirectional"))
      (node (ref "RCB0") (pin "2") (pinfunction "2_2") (pintype "passive"))
    )
    (net (code "6") (name "/CB0-1") (class "Default")
      (node (ref "CCB1-1") (pin "2") (pinfunction "2_2") (pintype "passive"))
      (node (ref "IC1") (pin "34") (pinfunction "CB0_34") (pintype "bidirectional"))
      (node (ref "RCB0-1") (pin "2") (pinfunction "2_2") (pintype "passive"))
    )
    (net (code "7") (name "/CB1") (class "Default")
      (node (ref "CCB1") (pin "1") (pinfunction "1_1") (pintype "passive"))
      (node (ref "CCB2") (pin "2") (pinfunction "2_2") (pintype "passive"))
      (node (ref "IC2") (pin "32") (pinfunction "CB1_32") (pintype "bidirectional"))
      (node (ref "RCB1") (pin "2") (pinfunction "2_2") (pintype "passive"))
    )
    (net (code "8") (name "/CB1-1") (class "Default")
      (node (ref "CCB1-1") (pin "1") (pinfunction "1_1") (pintype "passive"))
      (node (ref "CCB2-1") (pin "2") (pinfunction "2_2") (pintype "passive"))
      (node (ref "IC1") (pin "32") (pinfunction "CB1_32") (pintype "bidirectional"))
      (node (ref "RCB1-1") (pin "2") (pinfunction "2_2") (pintype "passive"))
    )
    (net (code "9") (name "/CB1-IN") (class "Default")
      (node (ref "LOW-IN") (pin "14") (pinfunction "14_14") (pintype "passive"))
      (node (ref "RCB1") (pin "1") (pinfunction "1_1") (pintype "passive"))
    )
    (net (code "10") (name "/CB1-IN-1") (class "Default")
      (node (ref "HIGH-IN") (pin "14") (pinfunction "14_14") (pintype "passive"))
      (node (ref "RCB1-1") (pin "1") (pinfunction "1_1") (pintype "passive"))
    )
    (net (code "11") (name "/CB2") (class "Default")
      (node (ref "CCB2") (pin "1") (pinfunction "1_1") (pintype "passive"))
      (node (ref "CCB3") (pin "2") (pinfunction "2_2") (pintype "passive"))
      (node (ref "IC2") (pin "30") (pinfunction "CB2_30") (pintype "bidirectional"))
      (node (ref "RCB2") (pin "2") (pinfunction "2_2") (pintype "passive"))
    )
    (net (code "12") (name "/CB2-1") (class "Default")
      (node (ref "CCB2-1") (pin "1") (pinfunction "1_1") (pintype "passive"))
      (node (ref "CCB3-1") (pin "2") (pinfunction "2_2") (pintype "passive"))
      (node (ref "IC1") (pin "30") (pinfunction "CB2_30") (pintype "bidirectional"))
      (node (ref "RCB2-1") (pin "2") (pinfunction "2_2") (pintype "passive"))
    )
    (net (code "13") (name "/CB2-IN") (class "Default")
      (node (ref "LOW-IN") (pin "16") (pinfunction "16_16") (pintype "passive"))
      (node (ref "RCB2") (pin "1") (pinfunction "1_1") (pintype "passive"))
    )
    (net (code "14") (name "/CB2-IN-1") (class "Default")
      (node (ref "HIGH-IN") (pin "16") (pinfunction "16_16") (pintype "passive"))
      (node (ref "RCB2-1") (pin "1") (pinfunction "1_1") (pintype "passive"))
    )
    (net (code "15") (name "/CB3") (class "Default")
      (node (ref "CCB3") (pin "1") (pinfunction "1_1") (pintype "passive"))
      (node (ref "CCB4") (pin "2") (pinfunction "2_2") (pintype "passive"))
      (node (ref "IC2") (pin "28") (pinfunction "CB3_28") (pintype "bidirectional"))
      (node (ref "RCB3") (pin "2") (pinfunction "2_2") (pintype "passive"))
    )
    (net (code "16") (name "/CB3-1") (class "Default")
      (node (ref "CCB3-1") (pin "1") (pinfunction "1_1") (pintype "passive"))
      (node (ref "CCB4-1") (pin "2") (pinfunction "2_2") (pintype "passive"))
      (node (ref "IC1") (pin "28") (pinfunction "CB3_28") (pintype "bidirectional"))
      (node (ref "RCB3-1") (pin "2") (pinfunction "2_2") (pintype "passive"))
    )
    (net (code "17") (name "/CB3-IN") (class "Default")
      (node (ref "LOW-IN") (pin "18") (pinfunction "18_18") (pintype "passive"))
      (node (ref "RCB3") (pin "1") (pinfunction "1_1") (pintype "passive"))
    )
    (net (code "18") (name "/CB3-IN-1") (class "Default")
      (node (ref "HIGH-IN") (pin "18") (pinfunction "18_18") (pintype "passive"))
      (node (ref "RCB3-1") (pin "1") (pinfunction "1_1") (pintype "passive"))
    )
    (net (code "19") (name "/CB4") (class "Default")
      (node (ref "CCB4") (pin "1") (pinfunction "1_1") (pintype "passive"))
      (node (ref "CCB5") (pin "2") (pinfunction "2_2") (pintype "passive"))
      (node (ref "IC2") (pin "26") (pinfunction "CB4_26") (pintype "bidirectional"))
      (node (ref "RCB4") (pin "2") (pinfunction "2_2") (pintype "passive"))
    )
    (net (code "20") (name "/CB4-1") (class "Default")
      (node (ref "CCB4-1") (pin "1") (pinfunction "1_1") (pintype "passive"))
      (node (ref "CCB5-1") (pin "2") (pinfunction "2_2") (pintype "passive"))
      (node (ref "IC1") (pin "26") (pinfunction "CB4_26") (pintype "bidirectional"))
      (node (ref "RCB4-1") (pin "2") (pinfunction "2_2") (pintype "passive"))
    )
    (net (code "21") (name "/CB4-IN") (class "Default")
      (node (ref "LOW-IN") (pin "20") (pinfunction "20_20") (pintype "passive"))
      (node (ref "RCB4") (pin "1") (pinfunction "1_1") (pintype "passive"))
    )
    (net (code "22") (name "/CB4-IN-1") (class "Default")
      (node (ref "HIGH-IN") (pin "20") (pinfunction "20_20") (pintype "passive"))
      (node (ref "RCB4-1") (pin "1") (pinfunction "1_1") (pintype "passive"))
    )
    (net (code "23") (name "/CB5") (class "Default")
      (node (ref "CCB5") (pin "1") (pinfunction "1_1") (pintype "passive"))
      (node (ref "CCB6") (pin "2") (pinfunction "2_2") (pintype "passive"))
      (node (ref "IC2") (pin "24") (pinfunction "CB5_24") (pintype "bidirectional"))
      (node (ref "RCB5") (pin "2") (pinfunction "2_2") (pintype "passive"))
    )
    (net (code "24") (name "/CB5-1") (class "Default")
      (node (ref "CCB5-1") (pin "1") (pinfunction "1_1") (pintype "passive"))
      (node (ref "CCB6-1") (pin "2") (pinfunction "2_2") (pintype "passive"))
      (node (ref "IC1") (pin "24") (pinfunction "CB5_24") (pintype "bidirectional"))
      (node (ref "RCB5-1") (pin "2") (pinfunction "2_2") (pintype "passive"))
    )
    (net (code "25") (name "/CB5-IN") (class "Default")
      (node (ref "LOW-IN") (pin "22") (pinfunction "22_22") (pintype "passive"))
      (node (ref "RCB5") (pin "1") (pinfunction "1_1") (pintype "passive"))
    )
    (net (code "26") (name "/CB5-IN-1") (class "Default")
      (node (ref "HIGH-IN") (pin "22") (pinfunction "22_22") (pintype "passive"))
      (node (ref "RCB5-1") (pin "1") (pinfunction "1_1") (pintype "passive"))
    )
    (net (code "27") (name "/CB6") (class "Default")
      (node (ref "CCB6") (pin "1") (pinfunction "1_1") (pintype "passive"))
      (node (ref "CCB7") (pin "2") (pinfunction "2_2") (pintype "passive"))
      (node (ref "IC2") (pin "22") (pinfunction "CB6_22") (pintype "bidirectional"))
      (node (ref "RCB6") (pin "2") (pinfunction "2_2") (pintype "passive"))
    )
    (net (code "28") (name "/CB6-1") (class "Default")
      (node (ref "CCB6-1") (pin "1") (pinfunction "1_1") (pintype "passive"))
      (node (ref "CCB7-1") (pin "2") (pinfunction "2_2") (pintype "passive"))
      (node (ref "IC1") (pin "22") (pinfunction "CB6_22") (pintype "bidirectional"))
      (node (ref "RCB6-1") (pin "2") (pinfunction "2_2") (pintype "passive"))
    )
    (net (code "29") (name "/CB6-IN") (class "Default")
      (node (ref "LOW-IN") (pin "24") (pinfunction "24_24") (pintype "passive"))
      (node (ref "RCB6") (pin "1") (pinfunction "1_1") (pintype "passive"))
    )
    (net (code "30") (name "/CB6-IN-1") (class "Default")
      (node (ref "HIGH-IN") (pin "24") (pinfunction "24_24") (pintype "passive"))
      (node (ref "RCB6-1") (pin "1") (pinfunction "1_1") (pintype "passive"))
    )
    (net (code "31") (name "/CB7") (class "Default")
      (node (ref "CCB7") (pin "1") (pinfunction "1_1") (pintype "passive"))
      (node (ref "CCB8") (pin "2") (pinfunction "2_2") (pintype "passive"))
      (node (ref "IC2") (pin "20") (pinfunction "CB7_20") (pintype "bidirectional"))
      (node (ref "RCB7") (pin "2") (pinfunction "2_2") (pintype "passive"))
    )
    (net (code "32") (name "/CB7-1") (class "Default")
      (node (ref "CCB7-1") (pin "1") (pinfunction "1_1") (pintype "passive"))
      (node (ref "CCB8-1") (pin "2") (pinfunction "2_2") (pintype "passive"))
      (node (ref "IC1") (pin "20") (pinfunction "CB7_20") (pintype "bidirectional"))
      (node (ref "RCB7-1") (pin "2") (pinfunction "2_2") (pintype "passive"))
    )
    (net (code "33") (name "/CB7-IN") (class "Default")
      (node (ref "LOW-IN") (pin "26") (pinfunction "26_26") (pintype "passive"))
      (node (ref "RCB7") (pin "1") (pinfunction "1_1") (pintype "passive"))
    )
    (net (code "34") (name "/CB7-IN-1") (class "Default")
      (node (ref "HIGH-IN") (pin "26") (pinfunction "26_26") (pintype "passive"))
      (node (ref "RCB7-1") (pin "1") (pinfunction "1_1") (pintype "passive"))
    )
    (net (code "35") (name "/CB8") (class "Default")
      (node (ref "CCB8") (pin "1") (pinfunction "1_1") (pintype "passive"))
      (node (ref "CCB9") (pin "2") (pinfunction "2_2") (pintype "passive"))
      (node (ref "IC2") (pin "18") (pinfunction "CB8_18") (pintype "bidirectional"))
      (node (ref "RCB8") (pin "2") (pinfunction "2_2") (pintype "passive"))
    )
    (net (code "36") (name "/CB8-1") (class "Default")
      (node (ref "CCB8-1") (pin "1") (pinfunction "1_1") (pintype "passive"))
      (node (ref "CCB9-1") (pin "2") (pinfunction "2_2") (pintype "passive"))
      (node (ref "IC1") (pin "18") (pinfunction "CB8_18") (pintype "bidirectional"))
      (node (ref "RCB8-1") (pin "2") (pinfunction "2_2") (pintype "passive"))
    )
    (net (code "37") (name "/CB8-IN") (class "Default")
      (node (ref "LOW-IN") (pin "28") (pinfunction "28_28") (pintype "passive"))
      (node (ref "RCB8") (pin "1") (pinfunction "1_1") (pintype "passive"))
    )
    (net (code "38") (name "/CB8-IN-1") (class "Default")
      (node (ref "HIGH-IN") (pin "28") (pinfunction "28_28") (pintype "passive"))
      (node (ref "RCB8-1") (pin "1") (pinfunction "1_1") (pintype "passive"))
    )
    (net (code "39") (name "/CB9") (class "Default")
      (node (ref "CCB10") (pin "2") (pinfunction "2_2") (pintype "passive"))
      (node (ref "CCB9") (pin "1") (pinfunction "1_1") (pintype "passive"))
      (node (ref "IC2") (pin "16") (pinfunction "CB9_16") (pintype "bidirectional"))
      (node (ref "RCB9") (pin "2") (pinfunction "2_2") (pintype "passive"))
    )
    (net (code "40") (name "/CB9-1") (class "Default")
      (node (ref "CCB10-1") (pin "2") (pinfunction "2_2") (pintype "passive"))
      (node (ref "CCB9-1") (pin "1") (pinfunction "1_1") (pintype "passive"))
      (node (ref "IC1") (pin "16") (pinfunction "CB9_16") (pintype "bidirectional"))
      (node (ref "RCB9-1") (pin "2") (pinfunction "2_2") (pintype "passive"))
    )
    (net (code "41") (name "/CB9-IN") (class "Default")
      (node (ref "LOW-IN") (pin "30") (pinfunction "30_30") (pintype "passive"))
      (node (ref "RCB9") (pin "1") (pinfunction "1_1") (pintype "passive"))
    )
    (net (code "42") (name "/CB9-IN-1") (class "Default")
      (node (ref "HIGH-IN") (pin "30") (pinfunction "30_30") (pintype "passive"))
      (node (ref "RCB9-1") (pin "1") (pinfunction "1_1") (pintype "passive"))
    )
    (net (code "43") (name "/CB10-1") (class "Default")
      (node (ref "CCB10-1") (pin "1") (pinfunction "1_1") (pintype "passive"))
      (node (ref "CCB11-1") (pin "2") (pinfunction "2_2") (pintype "passive"))
      (node (ref "IC1") (pin "14") (pinfunction "CB10_14") (pintype "bidirectional"))
      (node (ref "RCB10-1") (pin "2") (pinfunction "2_2") (pintype "passive"))
    )
    (net (code "44") (name "/CB10-IN") (class "Default")
      (node (ref "LOW-IN") (pin "32") (pinfunction "32_32") (pintype "passive"))
      (node (ref "RCB10") (pin "1") (pinfunction "1_1") (pintype "passive"))
    )
    (net (code "45") (name "/CB10-IN-1") (class "Default")
      (node (ref "HIGH-IN") (pin "32") (pinfunction "32_32") (pintype "passive"))
      (node (ref "RCB10-1") (pin "1") (pinfunction "1_1") (pintype "passive"))
    )
    (net (code "46") (name "/CB11-1") (class "Default")
      (node (ref "CCB11-1") (pin "1") (pinfunction "1_1") (pintype "passive"))
      (node (ref "CCB12-1") (pin "2") (pinfunction "2_2") (pintype "passive"))
      (node (ref "IC1") (pin "12") (pinfunction "CB11_12") (pintype "bidirectional"))
      (node (ref "RCB11-1") (pin "2") (pinfunction "2_2") (pintype "passive"))
    )
    (net (code "47") (name "/CB11-IN") (class "Default")
      (node (ref "LOW-IN") (pin "34") (pinfunction "34_34") (pintype "passive"))
      (node (ref "RCB11") (pin "1") (pinfunction "1_1") (pintype "passive"))
    )
    (net (code "48") (name "/CB11-IN-1") (class "Default")
      (node (ref "HIGH-IN") (pin "34") (pinfunction "34_34") (pintype "passive"))
      (node (ref "RCB11-1") (pin "1") (pinfunction "1_1") (pintype "passive"))
    )
    (net (code "49") (name "/CB12-1") (class "Default")
      (node (ref "CCB12-1") (pin "1") (pinfunction "1_1") (pintype "passive"))
      (node (ref "CCB13-1") (pin "2") (pinfunction "2_2") (pintype "passive"))
      (node (ref "IC1") (pin "10") (pinfunction "CB12_10") (pintype "bidirectional"))
      (node (ref "RCB12-1") (pin "2") (pinfunction "2_2") (pintype "passive"))
    )
    (net (code "50") (name "/CB12-IN") (class "Default")
      (node (ref "LOW-IN") (pin "36") (pinfunction "36_36") (pintype "passive"))
      (node (ref "RCB12") (pin "1") (pinfunction "1_1") (pintype "passive"))
    )
    (net (code "51") (name "/CB12-IN-1") (class "Default")
      (node (ref "HIGH-IN") (pin "36") (pinfunction "36_36") (pintype "passive"))
      (node (ref "RCB12-1") (pin "1") (pinfunction "1_1") (pintype "passive"))
    )
    (net (code "52") (name "/CB13-1") (class "Default")
      (node (ref "CCB13-1") (pin "1") (pinfunction "1_1") (pintype "passive"))
      (node (ref "CCB14-1") (pin "2") (pinfunction "2_2") (pintype "passive"))
      (node (ref "IC1") (pin "8") (pinfunction "CB13_8") (pintype "bidirectional"))
      (node (ref "RCB13-1") (pin "2") (pinfunction "2_2") (pintype "passive"))
    )
    (net (code "53") (name "/CB13-IN") (class "Default")
      (node (ref "LOW-IN") (pin "38") (pinfunction "38_38") (pintype "passive"))
      (node (ref "RCB13") (pin "1") (pinfunction "1_1") (pintype "passive"))
    )
    (net (code "54") (name "/CB13-IN-1") (class "Default")
      (node (ref "HIGH-IN") (pin "38") (pinfunction "38_38") (pintype "passive"))
      (node (ref "RCB13-1") (pin "1") (pinfunction "1_1") (pintype "passive"))
    )
    (net (code "55") (name "/CB14-1") (class "Default")
      (node (ref "CCB14-1") (pin "1") (pinfunction "1_1") (pintype "passive"))
      (node (ref "CCB15-1") (pin "2") (pinfunction "2_2") (pintype "passive"))
      (node (ref "IC1") (pin "6") (pinfunction "CB14_6") (pintype "bidirectional"))
      (node (ref "RCB14-1") (pin "2") (pinfunction "2_2") (pintype "passive"))
    )
    (net (code "56") (name "/COMHN") (class "Default")
      (node (ref "CBPH1") (pin "1") (pinfunction "1_1") (pintype "passive"))
      (node (ref "IC2") (pin "42") (pinfunction "COMHN_42") (pintype "bidirectional"))
      (node (ref "RCOMH1") (pin "2") (pinfunction "2_2") (pintype "passive"))
      (node (ref "RTERMH") (pin "1") (pinfunction "1_1") (pintype "passive"))
    )
    (net (code "57") (name "/COMHN-1") (class "Default")
      (node (ref "CCOMLN_BP-1") (pin "1") (pinfunction "1_1") (pintype "passive"))
      (node (ref "IC1") (pin "42") (pinfunction "COMHN_42") (pintype "bidirectional"))
      (node (ref "RCOMH1-1") (pin "2") (pinfunction "2_2") (pintype "passive"))
      (node (ref "RCOMML-1") (pin "1") (pinfunction "1_1") (pintype "passive"))
    )
    (net (code "58") (name "/COMHP") (class "Default")
      (node (ref "CBPH") (pin "1") (pinfunction "1_1") (pintype "passive"))
      (node (ref "IC2") (pin "43") (pinfunction "COMHP_43") (pintype "bidirectional"))
      (node (ref "RCOMH") (pin "2") (pinfunction "2_2") (pintype "passive"))
      (node (ref "RTERMH") (pin "2") (pinfunction "2_2") (pintype "passive"))
    )
    (net (code "59") (name "/COMHP-1") (class "Default")
      (node (ref "CCOMLP_BP-1") (pin "1") (pinfunction "1_1") (pintype "passive"))
      (node (ref "IC1") (pin "43") (pinfunction "COMHP_43") (pintype "bidirectional"))
      (node (ref "RCOMH-1") (pin "2") (pinfunction "2_2") (pintype "passive"))
      (node (ref "RCOMML-1") (pin "2") (pinfunction "2_2") (pintype "passive"))
    )
    (net (code "60") (name "/COMLN") (class "Default")
      (node (ref "CCOMLN_BP") (pin "1") (pinfunction "1_1") (pintype "passive"))
      (node (ref "IC2") (pin "41") (pinfunction "COMLN_41") (pintype "bidirectional"))
      (node (ref "RCOML1") (pin "2") (pinfunction "2_2") (pintype "passive"))
      (node (ref "RCOMML") (pin "2") (pinfunction "2_2") (pintype "passive"))
    )
    (net (code "61") (name "/COMLN-1") (class "Default")
      (node (ref "CBPL1") (pin "1") (pinfunction "1_1") (pintype "passive"))
      (node (ref "IC1") (pin "41") (pinfunction "COMLN_41") (pintype "bidirectional"))
      (node (ref "RCOML1-1") (pin "2") (pinfunction "2_2") (pintype "passive"))
      (node (ref "RTERML") (pin "2") (pinfunction "2_2") (pintype "passive"))
    )
    (net (code "62") (name "/COMLP") (class "Default")
      (node (ref "CCOMLP_BP") (pin "1") (pinfunction "1_1") (pintype "passive"))
      (node (ref "IC2") (pin "40") (pinfunction "COMLP_40") (pintype "bidirectional"))
      (node (ref "RCOML") (pin "2") (pinfunction "2_2") (pintype "passive"))
      (node (ref "RCOMML") (pin "1") (pinfunction "1_1") (pintype "passive"))
    )
    (net (code "63") (name "/COMLP-1") (class "Default")
      (node (ref "CBPL") (pin "1") (pinfunction "1_1") (pintype "passive"))
      (node (ref "IC1") (pin "40") (pinfunction "COMLP_40") (pintype "bidirectional"))
      (node (ref "RCOML-1") (pin "2") (pinfunction "2_2") (pintype "passive"))
      (node (ref "RTERML") (pin "1") (pinfunction "1_1") (pintype "passive"))
    )
    (net (code "64") (name "/CVDD") (class "Default")
      (node (ref "CCVDD") (pin "1") (pinfunction "1_1") (pintype "passive"))
      (node (ref "IC2") (pin "45") (pinfunction "CVDD_45") (pintype "bidirectional"))
      (node (ref "IC2") (pin "52") (pinfunction "RX_52") (pintype "bidirectional"))
    )
    (net (code "65") (name "/CVDD-1") (class "Default")
      (node (ref "CCVDD-1") (pin "1") (pinfunction "1_1") (pintype "passive"))
      (node (ref "IC1") (pin "45") (pinfunction "CVDD_45") (pintype "bidirectional"))
      (node (ref "IC1") (pin "52") (pinfunction "RX_52") (pintype "bidirectional"))
    )
    (net (code "66") (name "/DVDD") (class "Default")
      (node (ref "CDVDD") (pin "1") (pinfunction "1_1") (pintype "passive"))
      (node (ref "IC2") (pin "49") (pinfunction "DVDD_49") (pintype "bidirectional"))
    )
    (net (code "67") (name "/DVDD-1") (class "Default")
      (node (ref "CDVDD-1") (pin "1") (pinfunction "1_1") (pintype "passive"))
      (node (ref "IC1") (pin "49") (pinfunction "DVDD_49") (pintype "bidirectional"))
    )
    (net (code "68") (name "/GNDH") (class "Default")
      (node (ref "CAVDD-1") (pin "2") (pinfunction "2_2") (pintype "passive"))
      (node (ref "CBAT-1") (pin "1") (pinfunction "1_1") (pintype "passive"))
      (node (ref "CBPL") (pin "2") (pinfunction "2_2") (pintype "passive"))
      (node (ref "CBPL1") (pin "2") (pinfunction "2_2") (pintype "passive"))
      (node (ref "CCOMLN_BP-1") (pin "2") (pinfunction "2_2") (pintype "passive"))
      (node (ref "CCOMLP_BP-1") (pin "2") (pinfunction "2_2") (pintype "passive"))
      (node (ref "CCVDD-1") (pin "2") (pinfunction "2_2") (pintype "passive"))
      (node (ref "CDVDD-1") (pin "2") (pinfunction "2_2") (pintype "passive"))
      (node (ref "CLDOIN-1") (pin "2") (pinfunction "2_2") (pintype "passive"))
      (node (ref "CNEG5V-1") (pin "2") (pinfunction "2_2") (pintype "passive"))
      (node (ref "CNPN-1") (pin "1") (pinfunction "1_1") (pintype "passive"))
      (node (ref "CREFHP-1") (pin "2") (pinfunction "2_2") (pintype "passive"))
      (node (ref "CTEMP10") (pin "2") (pinfunction "2_2") (pintype "passive"))
      (node (ref "CTEMP11") (pin "2") (pinfunction "2_2") (pintype "passive"))
      (node (ref "CTEMP12") (pin "2") (pinfunction "2_2") (pintype "passive"))
      (node (ref "CTEMP13") (pin "2") (pinfunction "2_2") (pintype "passive"))
      (node (ref "CTEMP14") (pin "2") (pinfunction "2_2") (pintype "passive"))
      (node (ref "CTEMP15") (pin "2") (pinfunction "2_2") (pintype "passive"))
      (node (ref "CTEMP16") (pin "2") (pinfunction "2_2") (pintype "passive"))
      (node (ref "CTEMP9") (pin "2") (pinfunction "2_2") (pintype "passive"))
      (node (ref "CTSREF-1") (pin "2") (pinfunction "2_2") (pintype "passive"))
      (node (ref "CVC0-1") (pin "2") (pinfunction "2_2") (pintype "passive"))
      (node (ref "D2") (pin "3") (pinfunction "3_3") (pintype "bidirectional"))
      (node (ref "GNDH_PAD") (pin "1") (pinfunction "P_1") (pintype "passive"))
      (node (ref "HIGH-IN") (pin "01") (pinfunction "01_01") (pintype "passive"))
      (node (ref "HIGH-IN") (pin "02") (pinfunction "02_02") (pintype "passive"))
      (node (ref "HIGH-IN") (pin "12") (pinfunction "12_12") (pintype "passive"))
      (node (ref "IC1") (pin "36") (pinfunction "REFHM_36") (pintype "bidirectional"))
      (node (ref "IC1") (pin "39") (pinfunction "AVSS_39") (pintype "bidirectional"))
      (node (ref "IC1") (pin "46") (pinfunction "CVSS_46") (pintype "bidirectional"))
      (node (ref "IC1") (pin "50") (pinfunction "DVSS_50") (pintype "bidirectional"))
      (node (ref "IC1") (pin "65") (pinfunction "AVSS?_65") (pintype "bidirectional"))
      (node (ref "RCB0-1") (pin "1") (pinfunction "1_1") (pintype "passive"))
    )
    (net (code "69") (name "/GNDL") (class "Default")
      (node (ref "CAVDD") (pin "2") (pinfunction "2_2") (pintype "passive"))
      (node (ref "CBAT") (pin "1") (pinfunction "1_1") (pintype "passive"))
      (node (ref "CBPH") (pin "2") (pinfunction "2_2") (pintype "passive"))
      (node (ref "CBPH1") (pin "2") (pinfunction "2_2") (pintype "passive"))
      (node (ref "CCOMLN_BP") (pin "2") (pinfunction "2_2") (pintype "passive"))
      (node (ref "CCOMLP_BP") (pin "2") (pinfunction "2_2") (pintype "passive"))
      (node (ref "CCVDD") (pin "2") (pinfunction "2_2") (pintype "passive"))
      (node (ref "CDVDD") (pin "2") (pinfunction "2_2") (pintype "passive"))
      (node (ref "CLDOIN") (pin "2") (pinfunction "2_2") (pintype "passive"))
      (node (ref "CNEG5V") (pin "2") (pinfunction "2_2") (pintype "passive"))
      (node (ref "CNPN") (pin "1") (pinfunction "1_1") (pintype "passive"))
      (node (ref "CREFHP") (pin "2") (pinfunction "2_2") (pintype "passive"))
      (node (ref "CTEMP1") (pin "2") (pinfunction "2_2") (pintype "passive"))
      (node (ref "CTEMP2") (pin "2") (pinfunction "2_2") (pintype "passive"))
      (node (ref "CTEMP3") (pin "2") (pinfunction "2_2") (pintype "passive"))
      (node (ref "CTEMP4") (pin "2") (pinfunction "2_2") (pintype "passive"))
      (node (ref "CTEMP5") (pin "2") (pinfunction "2_2") (pintype "passive"))
      (node (ref "CTEMP6") (pin "2") (pinfunction "2_2") (pintype "passive"))
      (node (ref "CTEMP7") (pin "2") (pinfunction "2_2") (pintype "passive"))
      (node (ref "CTEMP8") (pin "2") (pinfunction "2_2") (pintype "passive"))
      (node (ref "CTSREF") (pin "2") (pinfunction "2_2") (pintype "passive"))
      (node (ref "CVC0") (pin "2") (pinfunction "2_2") (pintype "passive"))
      (node (ref "D1") (pin "3") (pinfunction "3_3") (pintype "bidirectional"))
      (node (ref "GNDL_PAD") (pin "1") (pinfunction "P_1") (pintype "passive"))
      (node (ref "IC2") (pin "36") (pinfunction "REFHM_36") (pintype "bidirectional"))
      (node (ref "IC2") (pin "39") (pinfunction "AVSS_39") (pintype "bidirectional"))
      (node (ref "IC2") (pin "46") (pinfunction "CVSS_46") (pintype "bidirectional"))
      (node (ref "IC2") (pin "50") (pinfunction "DVSS_50") (pintype "bidirectional"))
      (node (ref "IC2") (pin "65") (pinfunction "AVSS?_65") (pintype "bidirectional"))
      (node (ref "LOW-IN") (pin "01") (pinfunction "01_01") (pintype "passive"))
      (node (ref "LOW-IN") (pin "02") (pinfunction "02_02") (pintype "passive"))
      (node (ref "LOW-IN") (pin "12") (pinfunction "12_12") (pintype "passive"))
      (node (ref "RCB0") (pin "1") (pinfunction "1_1") (pintype "passive"))
    )
    (net (code "70") (name "/ISO_COMN") (class "Default")
      (node (ref "CISOL1") (pin "1") (pinfunction "1_1") (pintype "passive"))
      (node (ref "RCOML1-1") (pin "1") (pinfunction "1_1") (pintype "passive"))
    )
    (net (code "71") (name "/ISO_COMP") (class "Default")
      (node (ref "CISOL") (pin "1") (pinfunction "1_1") (pintype "passive"))
      (node (ref "RCOML-1") (pin "1") (pinfunction "1_1") (pintype "passive"))
    )
    (net (code "72") (name "/LDOIN") (class "Default")
      (node (ref "CLDOIN") (pin "1") (pinfunction "1_1") (pintype "passive"))
      (node (ref "IC2") (pin "47") (pinfunction "LDOIN_47") (pintype "bidirectional"))
      (node (ref "T1") (pin "E") (pinfunction "E_E") (pintype "passive"))
    )
    (net (code "73") (name "/LDOIN-1") (class "Default")
      (node (ref "CLDOIN-1") (pin "1") (pinfunction "1_1") (pintype "passive"))
      (node (ref "IC1") (pin "47") (pinfunction "LDOIN_47") (pintype "bidirectional"))
      (node (ref "T2") (pin "E") (pinfunction "E_E") (pintype "passive"))
    )
    (net (code "74") (name "/NC_VC_CB") (class "Default")
      (node (ref "CBAT") (pin "2") (pinfunction "2_2") (pintype "passive"))
      (node (ref "CCB15") (pin "1") (pinfunction "1_1") (pintype "passive"))
      (node (ref "IC2") (pin "1") (pinfunction "BAT_1") (pintype "bidirectional"))
      (node (ref "IC2") (pin "2") (pinfunction "CB16_2") (pintype "bidirectional"))
      (node (ref "IC2") (pin "3") (pinfunction "VC16_3") (pintype "bidirectional"))
      (node (ref "IC2") (pin "4") (pinfunction "CB15_4") (pintype "bidirectional"))
      (node (ref "IC2") (pin "5") (pinfunction "VC15_5") (pintype "bidirectional"))
      (node (ref "RBAT") (pin "2") (pinfunction "2_2") (pintype "passive"))
    )
    (net (code "75") (name "/NC_VC_CB_HIGH") (class "Default")
      (node (ref "CBAT-1") (pin "2") (pinfunction "2_2") (pintype "passive"))
      (node (ref "CCB15-1") (pin "1") (pinfunction "1_1") (pintype "passive"))
      (node (ref "IC1") (pin "1") (pinfunction "BAT_1") (pintype "bidirectional"))
      (node (ref "IC1") (pin "2") (pinfunction "CB16_2") (pintype "bidirectional"))
      (node (ref "IC1") (pin "3") (pinfunction "VC16_3") (pintype "bidirectional"))
      (node (ref "IC1") (pin "4") (pinfunction "CB15_4") (pintype "bidirectional"))
      (node (ref "IC1") (pin "5") (pinfunction "VC15_5") (pintype "bidirectional"))
      (node (ref "RBAT-1") (pin "2") (pinfunction "2_2") (pintype "passive"))
    )
    (net (code "76") (name "/NPNB") (class "Default")
      (node (ref "IC2") (pin "48") (pinfunction "NPNB_48") (pintype "bidirectional"))
      (node (ref "T1") (pin "B") (pinfunction "B_B") (pintype "passive"))
    )
    (net (code "77") (name "/NPNB-1") (class "Default")
      (node (ref "IC1") (pin "48") (pinfunction "NPNB_48") (pintype "bidirectional"))
      (node (ref "T2") (pin "B") (pinfunction "B_B") (pintype "passive"))
    )
    (net (code "78") (name "/REFHP") (class "Default")
      (node (ref "CREFHP") (pin "1") (pinfunction "1_1") (pintype "passive"))
      (node (ref "IC2") (pin "37") (pinfunction "REFHP_37") (pintype "bidirectional"))
    )
    (net (code "79") (name "/REFHP-1") (class "Default")
      (node (ref "CREFHP-1") (pin "1") (pinfunction "1_1") (pintype "passive"))
      (node (ref "IC1") (pin "37") (pinfunction "REFHP_37") (pintype "bidirectional"))
    )
    (net (code "80") (name "/SRN") (class "Default")
      (node (ref "CCS") (pin "1") (pinfunction "1_1") (pintype "passive"))
      (node (ref "IC2") (pin "63") (pinfunction "BBN(SRN)_63") (pintype "bidirectional"))
      (node (ref "RCS2") (pin "1") (pinfunction "1_1") (pintype "passive"))
    )
    (net (code "81") (name "/SRN-IN") (class "Default")
      (node (ref "RCS2") (pin "2") (pinfunction "2_2") (pintype "passive"))
      (node (ref "SR") (pin "3") (pinfunction "3_3") (pintype "passive"))
    )
    (net (code "82") (name "/SRP") (class "Default")
      (node (ref "CCS") (pin "2") (pinfunction "2_2") (pintype "passive"))
      (node (ref "IC2") (pin "64") (pinfunction "BBP(SRP)_64") (pintype "bidirectional"))
      (node (ref "RCS1") (pin "1") (pinfunction "1_1") (pintype "passive"))
    )
    (net (code "83") (name "/SRP-IN") (class "Default")
      (node (ref "RCS1") (pin "2") (pinfunction "2_2") (pintype "passive"))
      (node (ref "SR") (pin "4") (pinfunction "4_4") (pintype "passive"))
    )
    (net (code "84") (name "/TEMP1") (class "Default")
      (node (ref "CTEMP1") (pin "1") (pinfunction "1_1") (pintype "passive"))
      (node (ref "IC2") (pin "61") (pinfunction "GPIO1_61") (pintype "bidirectional"))
      (node (ref "LOW-IN") (pin "09") (pinfunction "09_09") (pintype "passive"))
      (node (ref "RTHRM1") (pin "2") (pinfunction "2_2") (pintype "passive"))
    )
    (net (code "85") (name "/TEMP2") (class "Default")
      (node (ref "CTEMP2") (pin "1") (pinfunction "1_1") (pintype "passive"))
      (node (ref "IC2") (pin "60") (pinfunction "GPIO2_60") (pintype "bidirectional"))
      (node (ref "LOW-IN") (pin "10") (pinfunction "10_10") (pintype "passive"))
      (node (ref "RTHRM2") (pin "2") (pinfunction "2_2") (pintype "passive"))
    )
    (net (code "86") (name "/TEMP3") (class "Default")
      (node (ref "CTEMP3") (pin "1") (pinfunction "1_1") (pintype "passive"))
      (node (ref "IC2") (pin "59") (pinfunction "GPIO3_59") (pintype "bidirectional"))
      (node (ref "LOW-IN") (pin "07") (pinfunction "07_07") (pintype "passive"))
      (node (ref "RTHRM3") (pin "2") (pinfunction "2_2") (pintype "passive"))
    )
    (net (code "87") (name "/TEMP4") (class "Default")
      (node (ref "CTEMP4") (pin "1") (pinfunction "1_1") (pintype "passive"))
      (node (ref "IC2") (pin "58") (pinfunction "GPIO4_58") (pintype "bidirectional"))
      (node (ref "LOW-IN") (pin "08") (pinfunction "08_08") (pintype "passive"))
      (node (ref "RTHRM4") (pin "2") (pinfunction "2_2") (pintype "passive"))
    )
    (net (code "88") (name "/TEMP5") (class "Default")
      (node (ref "CTEMP5") (pin "1") (pinfunction "1_1") (pintype "passive"))
      (node (ref "IC2") (pin "57") (pinfunction "GPIO5_57") (pintype "bidirectional"))
      (node (ref "LOW-IN") (pin "05") (pinfunction "05_05") (pintype "passive"))
      (node (ref "RTHRM5") (pin "2") (pinfunction "2_2") (pintype "passive"))
    )
    (net (code "89") (name "/TEMP6") (class "Default")
      (node (ref "CTEMP6") (pin "1") (pinfunction "1_1") (pintype "passive"))
      (node (ref "IC2") (pin "56") (pinfunction "GPIO6_56") (pintype "bidirectional"))
      (node (ref "LOW-IN") (pin "06") (pinfunction "06_06") (pintype "passive"))
      (node (ref "RTHRM6") (pin "2") (pinfunction "2_2") (pintype "passive"))
    )
    (net (code "90") (name "/TEMP7") (class "Default")
      (node (ref "CTEMP7") (pin "1") (pinfunction "1_1") (pintype "passive"))
      (node (ref "IC2") (pin "55") (pinfunction "GPIO7_55") (pintype "bidirectional"))
      (node (ref "LOW-IN") (pin "03") (pinfunction "03_03") (pintype "passive"))
      (node (ref "RTHRM7") (pin "2") (pinfunction "2_2") (pintype "passive"))
    )
    (net (code "91") (name "/TEMP8") (class "Default")
      (node (ref "CTEMP8") (pin "1") (pinfunction "1_1") (pintype "passive"))
      (node (ref "IC2") (pin "54") (pinfunction "GPIO8_54") (pintype "bidirectional"))
      (node (ref "LOW-IN") (pin "04") (pinfunction "04_04") (pintype "passive"))
      (node (ref "RTHRM8") (pin "2") (pinfunction "2_2") (pintype "passive"))
    )
    (net (code "92") (name "/TEMP9") (class "Default")
      (node (ref "CTEMP9") (pin "1") (pinfunction "1_1") (pintype "passive"))
      (node (ref "HIGH-IN") (pin "09") (pinfunction "09_09") (pintype "passive"))
      (node (ref "IC1") (pin "61") (pinfunction "GPIO1_61") (pintype "bidirectional"))
      (node (ref "RTHRM1-1") (pin "2") (pinfunction "2_2") (pintype "passive"))
    )
    (net (code "93") (name "/TEMP10") (class "Default")
      (node (ref "CTEMP10") (pin "1") (pinfunction "1_1") (pintype "passive"))
      (node (ref "HIGH-IN") (pin "10") (pinfunction "10_10") (pintype "passive"))
      (node (ref "IC1") (pin "60") (pinfunction "GPIO2_60") (pintype "bidirectional"))
      (node (ref "RTHRM2-1") (pin "2") (pinfunction "2_2") (pintype "passive"))
    )
    (net (code "94") (name "/TEMP11") (class "Default")
      (node (ref "CTEMP11") (pin "1") (pinfunction "1_1") (pintype "passive"))
      (node (ref "HIGH-IN") (pin "07") (pinfunction "07_07") (pintype "passive"))
      (node (ref "IC1") (pin "59") (pinfunction "GPIO3_59") (pintype "bidirectional"))
      (node (ref "RTHRM3-1") (pin "2") (pinfunction "2_2") (pintype "passive"))
    )
    (net (code "95") (name "/TEMP12") (class "Default")
      (node (ref "CTEMP12") (pin "1") (pinfunction "1_1") (pintype "passive"))
      (node (ref "HIGH-IN") (pin "08") (pinfunction "08_08") (pintype "passive"))
      (node (ref "IC1") (pin "58") (pinfunction "GPIO4_58") (pintype "bidirectional"))
      (node (ref "RTHRM4-1") (pin "2") (pinfunction "2_2") (pintype "passive"))
    )
    (net (code "96") (name "/TEMP13") (class "Default")
      (node (ref "CTEMP13") (pin "1") (pinfunction "1_1") (pintype "passive"))
      (node (ref "HIGH-IN") (pin "05") (pinfunction "05_05") (pintype "passive"))
      (node (ref "IC1") (pin "57") (pinfunction "GPIO5_57") (pintype "bidirectional"))
      (node (ref "RTHRM5-1") (pin "2") (pinfunction "2_2") (pintype "passive"))
    )
    (net (code "97") (name "/TEMP14") (class "Default")
      (node (ref "CTEMP14") (pin "1") (pinfunction "1_1") (pintype "passive"))
      (node (ref "HIGH-IN") (pin "06") (pinfunction "06_06") (pintype "passive"))
      (node (ref "IC1") (pin "56") (pinfunction "GPIO6_56") (pintype "bidirectional"))
      (node (ref "RTHRM6-1") (pin "2") (pinfunction "2_2") (pintype "passive"))
    )
    (net (code "98") (name "/TEMP15") (class "Default")
      (node (ref "CTEMP15") (pin "1") (pinfunction "1_1") (pintype "passive"))
      (node (ref "HIGH-IN") (pin "03") (pinfunction "03_03") (pintype "passive"))
      (node (ref "IC1") (pin "55") (pinfunction "GPIO7_55") (pintype "bidirectional"))
      (node (ref "RTHRM7-1") (pin "2") (pinfunction "2_2") (pintype "passive"))
    )
    (net (code "99") (name "/TEMP16") (class "Default")
      (node (ref "CTEMP16") (pin "1") (pinfunction "1_1") (pintype "passive"))
      (node (ref "HIGH-IN") (pin "04") (pinfunction "04_04") (pintype "passive"))
      (node (ref "IC1") (pin "54") (pinfunction "GPIO8_54") (pintype "bidirectional"))
      (node (ref "RTHRM8-1") (pin "2") (pinfunction "2_2") (pintype "passive"))
    )
    (net (code "100") (name "/TP") (class "Default")
      (node (ref "IC2") (pin "62") (pinfunction "NFAULT_62") (pintype "bidirectional"))
      (node (ref "TP_NFAUL") (pin "TP") (pinfunction "TP_TP") (pintype "input"))
    )
    (net (code "101") (name "/TP-1") (class "Default")
      (node (ref "IC1") (pin "62") (pinfunction "NFAULT_62") (pintype "bidirectional"))
      (node (ref "TP_NFAUL-1") (pin "TP") (pinfunction "TP_TP") (pintype "input"))
    )
    (net (code "102") (name "/TSREF") (class "Default")
      (node (ref "CTSREF") (pin "1") (pinfunction "1_1") (pintype "passive"))
      (node (ref "IC2") (pin "51") (pinfunction "TSREF_51") (pintype "bidirectional"))
      (node (ref "RTHRM1") (pin "1") (pinfunction "1_1") (pintype "passive"))
      (node (ref "RTHRM2") (pin "1") (pinfunction "1_1") (pintype "passive"))
      (node (ref "RTHRM3") (pin "1") (pinfunction "1_1") (pintype "passive"))
      (node (ref "RTHRM4") (pin "1") (pinfunction "1_1") (pintype "passive"))
      (node (ref "RTHRM5") (pin "1") (pinfunction "1_1") (pintype "passive"))
      (node (ref "RTHRM6") (pin "1") (pinfunction "1_1") (pintype "passive"))
      (node (ref "RTHRM7") (pin "1") (pinfunction "1_1") (pintype "passive"))
      (node (ref "RTHRM8") (pin "1") (pinfunction "1_1") (pintype "passive"))
    )
    (net (code "103") (name "/TSREF-1") (class "Default")
      (node (ref "CTSREF-1") (pin "1") (pinfunction "1_1") (pintype "passive"))
      (node (ref "IC1") (pin "51") (pinfunction "TSREF_51") (pintype "bidirectional"))
      (node (ref "RTHRM1-1") (pin "1") (pinfunction "1_1") (pintype "passive"))
      (node (ref "RTHRM2-1") (pin "1") (pinfunction "1_1") (pintype "passive"))
      (node (ref "RTHRM3-1") (pin "1") (pinfunction "1_1") (pintype "passive"))
      (node (ref "RTHRM4-1") (pin "1") (pinfunction "1_1") (pintype "passive"))
      (node (ref "RTHRM5-1") (pin "1") (pinfunction "1_1") (pintype "passive"))
      (node (ref "RTHRM6-1") (pin "1") (pinfunction "1_1") (pintype "passive"))
      (node (ref "RTHRM7-1") (pin "1") (pinfunction "1_1") (pintype "passive"))
      (node (ref "RTHRM8-1") (pin "1") (pinfunction "1_1") (pintype "passive"))
    )
    (net (code "104") (name "/VC0") (class "Default")
      (node (ref "CVC0") (pin "1") (pinfunction "1_1") (pintype "passive"))
      (node (ref "CVC1") (pin "2") (pinfunction "2_2") (pintype "passive"))
      (node (ref "IC2") (pin "35") (pinfunction "VC0_35") (pintype "bidirectional"))
      (node (ref "RVC0") (pin "2") (pinfunction "2_2") (pintype "passive"))
    )
    (net (code "105") (name "/VC0-1") (class "Default")
      (node (ref "CVC0-1") (pin "1") (pinfunction "1_1") (pintype "passive"))
      (node (ref "CVC1-1") (pin "2") (pinfunction "2_2") (pintype "passive"))
      (node (ref "IC1") (pin "35") (pinfunction "VC0_35") (pintype "bidirectional"))
      (node (ref "RVC0-1") (pin "2") (pinfunction "2_2") (pintype "passive"))
    )
    (net (code "106") (name "/VC0-IN") (class "Default")
      (node (ref "LOW-IN") (pin "11") (pinfunction "11_11") (pintype "passive"))
      (node (ref "RVC0") (pin "1") (pinfunction "1_1") (pintype "passive"))
    )
    (net (code "107") (name "/VC0-IN-1") (class "Default")
      (node (ref "HIGH-IN") (pin "11") (pinfunction "11_11") (pintype "passive"))
      (node (ref "RVC0-1") (pin "1") (pinfunction "1_1") (pintype "passive"))
    )
    (net (code "108") (name "/VC1") (class "Default")
      (node (ref "CVC1") (pin "1") (pinfunction "1_1") (pintype "passive"))
      (node (ref "CVC2") (pin "2") (pinfunction "2_2") (pintype "passive"))
      (node (ref "IC2") (pin "33") (pinfunction "VC1_33") (pintype "bidirectional"))
      (node (ref "RVC1") (pin "2") (pinfunction "2_2") (pintype "passive"))
    )
    (net (code "109") (name "/VC1-1") (class "Default")
      (node (ref "CVC1-1") (pin "1") (pinfunction "1_1") (pintype "passive"))
      (node (ref "CVC2-1") (pin "2") (pinfunction "2_2") (pintype "passive"))
      (node (ref "IC1") (pin "33") (pinfunction "VC1_33") (pintype "bidirectional"))
      (node (ref "RVC1-1") (pin "2") (pinfunction "2_2") (pintype "passive"))
    )
    (net (code "110") (name "/VC1-IN") (class "Default")
      (node (ref "LOW-IN") (pin "13") (pinfunction "13_13") (pintype "passive"))
      (node (ref "RVC1") (pin "1") (pinfunction "1_1") (pintype "passive"))
    )
    (net (code "111") (name "/VC1-IN-1") (class "Default")
      (node (ref "HIGH-IN") (pin "13") (pinfunction "13_13") (pintype "passive"))
      (node (ref "RVC1-1") (pin "1") (pinfunction "1_1") (pintype "passive"))
    )
    (net (code "112") (name "/VC2") (class "Default")
      (node (ref "CVC2") (pin "1") (pinfunction "1_1") (pintype "passive"))
      (node (ref "CVC3") (pin "2") (pinfunction "2_2") (pintype "passive"))
      (node (ref "IC2") (pin "31") (pinfunction "VC2_31") (pintype "bidirectional"))
      (node (ref "RVC2") (pin "2") (pinfunction "2_2") (pintype "passive"))
    )
    (net (code "113") (name "/VC2-1") (class "Default")
      (node (ref "CVC2-1") (pin "1") (pinfunction "1_1") (pintype "passive"))
      (node (ref "CVC3-1") (pin "2") (pinfunction "2_2") (pintype "passive"))
      (node (ref "IC1") (pin "31") (pinfunction "VC2_31") (pintype "bidirectional"))
      (node (ref "RVC2-1") (pin "2") (pinfunction "2_2") (pintype "passive"))
    )
    (net (code "114") (name "/VC2-IN") (class "Default")
      (node (ref "LOW-IN") (pin "15") (pinfunction "15_15") (pintype "passive"))
      (node (ref "RVC2") (pin "1") (pinfunction "1_1") (pintype "passive"))
    )
    (net (code "115") (name "/VC2-IN-1") (class "Default")
      (node (ref "HIGH-IN") (pin "15") (pinfunction "15_15") (pintype "passive"))
      (node (ref "RVC2-1") (pin "1") (pinfunction "1_1") (pintype "passive"))
    )
    (net (code "116") (name "/VC3") (class "Default")
      (node (ref "CVC3") (pin "1") (pinfunction "1_1") (pintype "passive"))
      (node (ref "CVC4") (pin "2") (pinfunction "2_2") (pintype "passive"))
      (node (ref "IC2") (pin "29") (pinfunction "VC3_29") (pintype "bidirectional"))
      (node (ref "RVC3") (pin "2") (pinfunction "2_2") (pintype "passive"))
    )
    (net (code "117") (name "/VC3-1") (class "Default")
      (node (ref "CVC3-1") (pin "1") (pinfunction "1_1") (pintype "passive"))
      (node (ref "CVC4-1") (pin "2") (pinfunction "2_2") (pintype "passive"))
      (node (ref "IC1") (pin "29") (pinfunction "VC3_29") (pintype "bidirectional"))
      (node (ref "RVC3-1") (pin "2") (pinfunction "2_2") (pintype "passive"))
    )
    (net (code "118") (name "/VC3-IN") (class "Default")
      (node (ref "LOW-IN") (pin "17") (pinfunction "17_17") (pintype "passive"))
      (node (ref "RVC3") (pin "1") (pinfunction "1_1") (pintype "passive"))
    )
    (net (code "119") (name "/VC3-IN-1") (class "Default")
      (node (ref "HIGH-IN") (pin "17") (pinfunction "17_17") (pintype "passive"))
      (node (ref "RVC3-1") (pin "1") (pinfunction "1_1") (pintype "passive"))
    )
    (net (code "120") (name "/VC4") (class "Default")
      (node (ref "CVC4") (pin "1") (pinfunction "1_1") (pintype "passive"))
      (node (ref "CVC5") (pin "2") (pinfunction "2_2") (pintype "passive"))
      (node (ref "IC2") (pin "27") (pinfunction "VC4_27") (pintype "bidirectional"))
      (node (ref "RVC4") (pin "2") (pinfunction "2_2") (pintype "passive"))
    )
    (net (code "121") (name "/VC4-1") (class "Default")
      (node (ref "CVC4-1") (pin "1") (pinfunction "1_1") (pintype "passive"))
      (node (ref "CVC5-1") (pin "2") (pinfunction "2_2") (pintype "passive"))
      (node (ref "IC1") (pin "27") (pinfunction "VC4_27") (pintype "bidirectional"))
      (node (ref "RVC4-1") (pin "2") (pinfunction "2_2") (pintype "passive"))
    )
    (net (code "122") (name "/VC4-IN") (class "Default")
      (node (ref "LOW-IN") (pin "19") (pinfunction "19_19") (pintype "passive"))
      (node (ref "RVC4") (pin "1") (pinfunction "1_1") (pintype "passive"))
    )
    (net (code "123") (name "/VC4-IN-1") (class "Default")
      (node (ref "HIGH-IN") (pin "19") (pinfunction "19_19") (pintype "passive"))
      (node (ref "RVC4-1") (pin "1") (pinfunction "1_1") (pintype "passive"))
    )
    (net (code "124") (name "/VC5") (class "Default")
      (node (ref "CVC5") (pin "1") (pinfunction "1_1") (pintype "passive"))
      (node (ref "CVC6") (pin "2") (pinfunction "2_2") (pintype "passive"))
      (node (ref "IC2") (pin "25") (pinfunction "VC5_25") (pintype "bidirectional"))
      (node (ref "RVC5") (pin "2") (pinfunction "2_2") (pintype "passive"))
    )
    (net (code "125") (name "/VC5-1") (class "Default")
      (node (ref "CVC5-1") (pin "1") (pinfunction "1_1") (pintype "passive"))
      (node (ref "CVC6-1") (pin "2") (pinfunction "2_2") (pintype "passive"))
      (node (ref "IC1") (pin "25") (pinfunction "VC5_25") (pintype "bidirectional"))
      (node (ref "RVC5-1") (pin "2") (pinfunction "2_2") (pintype "passive"))
    )
    (net (code "126") (name "/VC5-IN") (class "Default")
      (node (ref "LOW-IN") (pin "21") (pinfunction "21_21") (pintype "passive"))
      (node (ref "RVC5") (pin "1") (pinfunction "1_1") (pintype "passive"))
    )
    (net (code "127") (name "/VC5-IN-1") (class "Default")
      (node (ref "HIGH-IN") (pin "21") (pinfunction "21_21") (pintype "passive"))
      (node (ref "RVC5-1") (pin "1") (pinfunction "1_1") (pintype "passive"))
    )
    (net (code "128") (name "/VC6") (class "Default")
      (node (ref "CVC6") (pin "1") (pinfunction "1_1") (pintype "passive"))
      (node (ref "CVC7") (pin "2") (pinfunction "2_2") (pintype "passive"))
      (node (ref "IC2") (pin "23") (pinfunction "VC6_23") (pintype "bidirectional"))
      (node (ref "RVC6") (pin "2") (pinfunction "2_2") (pintype "passive"))
    )
    (net (code "129") (name "/VC6-1") (class "Default")
      (node (ref "CVC6-1") (pin "1") (pinfunction "1_1") (pintype "passive"))
      (node (ref "CVC7-1") (pin "2") (pinfunction "2_2") (pintype "passive"))
      (node (ref "IC1") (pin "23") (pinfunction "VC6_23") (pintype "bidirectional"))
      (node (ref "RVC6-1") (pin "2") (pinfunction "2_2") (pintype "passive"))
    )
    (net (code "130") (name "/VC6-IN") (class "Default")
      (node (ref "LOW-IN") (pin "23") (pinfunction "23_23") (pintype "passive"))
      (node (ref "RVC6") (pin "1") (pinfunction "1_1") (pintype "passive"))
    )
    (net (code "131") (name "/VC6-IN-1") (class "Default")
      (node (ref "HIGH-IN") (pin "23") (pinfunction "23_23") (pintype "passive"))
      (node (ref "RVC6-1") (pin "1") (pinfunction "1_1") (pintype "passive"))
    )
    (net (code "132") (name "/VC7") (class "Default")
      (node (ref "CVC7") (pin "1") (pinfunction "1_1") (pintype "passive"))
      (node (ref "CVC8") (pin "2") (pinfunction "2_2") (pintype "passive"))
      (node (ref "IC2") (pin "21") (pinfunction "VC7_21") (pintype "bidirectional"))
      (node (ref "RVC7") (pin "2") (pinfunction "2_2") (pintype "passive"))
    )
    (net (code "133") (name "/VC7-1") (class "Default")
      (node (ref "CVC7-1") (pin "1") (pinfunction "1_1") (pintype "passive"))
      (node (ref "CVC8-1") (pin "2") (pinfunction "2_2") (pintype "passive"))
      (node (ref "IC1") (pin "21") (pinfunction "VC7_21") (pintype "bidirectional"))
      (node (ref "RVC7-1") (pin "2") (pinfunction "2_2") (pintype "passive"))
    )
    (net (code "134") (name "/VC7-IN") (class "Default")
      (node (ref "LOW-IN") (pin "25") (pinfunction "25_25") (pintype "passive"))
      (node (ref "RVC7") (pin "1") (pinfunction "1_1") (pintype "passive"))
    )
    (net (code "135") (name "/VC7-IN-1") (class "Default")
      (node (ref "HIGH-IN") (pin "25") (pinfunction "25_25") (pintype "passive"))
      (node (ref "RVC7-1") (pin "1") (pinfunction "1_1") (pintype "passive"))
    )
    (net (code "136") (name "/VC8") (class "Default")
      (node (ref "CVC8") (pin "1") (pinfunction "1_1") (pintype "passive"))
      (node (ref "CVC9") (pin "2") (pinfunction "2_2") (pintype "passive"))
      (node (ref "IC2") (pin "19") (pinfunction "VC8_19") (pintype "bidirectional"))
      (node (ref "RVC8") (pin "2") (pinfunction "2_2") (pintype "passive"))
    )
    (net (code "137") (name "/VC8-1") (class "Default")
      (node (ref "CVC8-1") (pin "1") (pinfunction "1_1") (pintype "passive"))
      (node (ref "CVC9-1") (pin "2") (pinfunction "2_2") (pintype "passive"))
      (node (ref "IC1") (pin "19") (pinfunction "VC8_19") (pintype "bidirectional"))
      (node (ref "RVC8-1") (pin "2") (pinfunction "2_2") (pintype "passive"))
    )
    (net (code "138") (name "/VC8-IN") (class "Default")
      (node (ref "LOW-IN") (pin "27") (pinfunction "27_27") (pintype "passive"))
      (node (ref "RVC8") (pin "1") (pinfunction "1_1") (pintype "passive"))
    )
    (net (code "139") (name "/VC8-IN-1") (class "Default")
      (node (ref "HIGH-IN") (pin "27") (pinfunction "27_27") (pintype "passive"))
      (node (ref "RVC8-1") (pin "1") (pinfunction "1_1") (pintype "passive"))
    )
    (net (code "140") (name "/VC9") (class "Default")
      (node (ref "CVC10") (pin "2") (pinfunction "2_2") (pintype "passive"))
      (node (ref "CVC9") (pin "1") (pinfunction "1_1") (pintype "passive"))
      (node (ref "IC2") (pin "17") (pinfunction "VC9_17") (pintype "bidirectional"))
      (node (ref "RVC9") (pin "2") (pinfunction "2_2") (pintype "passive"))
    )
    (net (code "141") (name "/VC9-1") (class "Default")
      (node (ref "CVC10-1") (pin "2") (pinfunction "2_2") (pintype "passive"))
      (node (ref "CVC9-1") (pin "1") (pinfunction "1_1") (pintype "passive"))
      (node (ref "IC1") (pin "17") (pinfunction "VC9_17") (pintype "bidirectional"))
      (node (ref "RVC9-1") (pin "2") (pinfunction "2_2") (pintype "passive"))
    )
    (net (code "142") (name "/VC9-IN") (class "Default")
      (node (ref "LOW-IN") (pin "29") (pinfunction "29_29") (pintype "passive"))
      (node (ref "RVC9") (pin "1") (pinfunction "1_1") (pintype "passive"))
    )
    (net (code "143") (name "/VC9-IN-1") (class "Default")
      (node (ref "HIGH-IN") (pin "29") (pinfunction "29_29") (pintype "passive"))
      (node (ref "RVC9-1") (pin "1") (pinfunction "1_1") (pintype "passive"))
    )
    (net (code "144") (name "/VC10-1") (class "Default")
      (node (ref "CVC10-1") (pin "1") (pinfunction "1_1") (pintype "passive"))
      (node (ref "CVC11-1") (pin "2") (pinfunction "2_2") (pintype "passive"))
      (node (ref "IC1") (pin "15") (pinfunction "VC10_15") (pintype "bidirectional"))
      (node (ref "RVC10-1") (pin "2") (pinfunction "2_2") (pintype "passive"))
    )
    (net (code "145") (name "/VC10-IN") (class "Default")
      (node (ref "LOW-IN") (pin "31") (pinfunction "31_31") (pintype "passive"))
      (node (ref "RVC10") (pin "1") (pinfunction "1_1") (pintype "passive"))
    )
    (net (code "146") (name "/VC10-IN-1") (class "Default")
      (node (ref "HIGH-IN") (pin "31") (pinfunction "31_31") (pintype "passive"))
      (node (ref "RVC10-1") (pin "1") (pinfunction "1_1") (pintype "passive"))
    )
    (net (code "147") (name "/VC11-1") (class "Default")
      (node (ref "CVC11-1") (pin "1") (pinfunction "1_1") (pintype "passive"))
      (node (ref "CVC12-1") (pin "2") (pinfunction "2_2") (pintype "passive"))
      (node (ref "IC1") (pin "13") (pinfunction "VC11_13") (pintype "bidirectional"))
      (node (ref "RVC11-1") (pin "2") (pinfunction "2_2") (pintype "passive"))
    )
    (net (code "148") (name "/VC11-IN") (class "Default")
      (node (ref "LOW-IN") (pin "33") (pinfunction "33_33") (pintype "passive"))
      (node (ref "RVC11") (pin "1") (pinfunction "1_1") (pintype "passive"))
    )
    (net (code "149") (name "/VC11-IN-1") (class "Default")
      (node (ref "HIGH-IN") (pin "33") (pinfunction "33_33") (pintype "passive"))
      (node (ref "RVC11-1") (pin "1") (pinfunction "1_1") (pintype "passive"))
    )
    (net (code "150") (name "/VC12-1") (class "Default")
      (node (ref "CVC12-1") (pin "1") (pinfunction "1_1") (pintype "passive"))
      (node (ref "CVC13-1") (pin "2") (pinfunction "2_2") (pintype "passive"))
      (node (ref "IC1") (pin "11") (pinfunction "VC12_11") (pintype "bidirectional"))
      (node (ref "RVC12-1") (pin "2") (pinfunction "2_2") (pintype "passive"))
    )
    (net (code "151") (name "/VC12-IN") (class "Default")
      (node (ref "LOW-IN") (pin "35") (pinfunction "35_35") (pintype "passive"))
      (node (ref "RVC12") (pin "1") (pinfunction "1_1") (pintype "passive"))
    )
    (net (code "152") (name "/VC12-IN-1") (class "Default")
      (node (ref "HIGH-IN") (pin "35") (pinfunction "35_35") (pintype "passive"))
      (node (ref "RVC12-1") (pin "1") (pinfunction "1_1") (pintype "passive"))
    )
    (net (code "153") (name "/VC13-1") (class "Default")
      (node (ref "CVC13-1") (pin "1") (pinfunction "1_1") (pintype "passive"))
      (node (ref "CVC14-1") (pin "2") (pinfunction "2_2") (pintype "passive"))
      (node (ref "IC1") (pin "9") (pinfunction "VC13_9") (pintype "bidirectional"))
      (node (ref "RVC13-1") (pin "2") (pinfunction "2_2") (pintype "passive"))
    )
    (net (code "154") (name "/VC13-IN") (class "Default")
      (node (ref "LOW-IN") (pin "37") (pinfunction "37_37") (pintype "passive"))
      (node (ref "RVC13") (pin "1") (pinfunction "1_1") (pintype "passive"))
    )
    (net (code "155") (name "/VC13-IN-1") (class "Default")
      (node (ref "HIGH-IN") (pin "37") (pinfunction "37_37") (pintype "passive"))
      (node (ref "RVC13-1") (pin "1") (pinfunction "1_1") (pintype "passive"))
    )
    (net (code "156") (name "/VC14-1") (class "Default")
      (node (ref "CVC14-1") (pin "1") (pinfunction "1_1") (pintype "passive"))
      (node (ref "IC1") (pin "7") (pinfunction "VC14_7") (pintype "bidirectional"))
      (node (ref "RVC14-1") (pin "2") (pinfunction "2_2") (pintype "passive"))
    )
    (net (code "157") (name "/VC14-IN") (class "Default")
      (node (ref "LOW-IN") (pin "39") (pinfunction "39_39") (pintype "passive"))
      (node (ref "RVC14") (pin "1") (pinfunction "1_1") (pintype "passive"))
    )
    (net (code "158") (name "/VC14-IN-1") (class "Default")
      (node (ref "HIGH-IN") (pin "39") (pinfunction "39_39") (pintype "passive"))
      (node (ref "RVC14-1") (pin "1") (pinfunction "1_1") (pintype "passive"))
    )
    (net (code "159") (name "Net-(CCOMHN-Pad1)") (class "Default")
      (node (ref "CCOMHN") (pin "1") (pinfunction "1_1") (pintype "passive"))
      (node (ref "COMMH") (pin "4") (pinfunction "4_4") (pintype "passive"))
    )
    (net (code "160") (name "Net-(CCOMHN-Pad2)") (class "Default")
      (node (ref "CCOMHN") (pin "2") (pinfunction "2_2") (pintype "passive"))
      (node (ref "D2") (pin "2") (pinfunction "2_2") (pintype "bidirectional"))
      (node (ref "RCOMH1-1") (pin "1") (pinfunction "1_1") (pintype "passive"))
    )
    (net (code "161") (name "Net-(CCOMHP-Pad1)") (class "Default")
      (node (ref "CCOMHP") (pin "1") (pinfunction "1_1") (pintype "passive"))
      (node (ref "COMMH") (pin "2") (pinfunction "2_2") (pintype "passive"))
    )
    (net (code "162") (name "Net-(CCOMHP-Pad2)") (class "Default")
      (node (ref "CCOMHP") (pin "2") (pinfunction "2_2") (pintype "passive"))
      (node (ref "D2") (pin "1") (pinfunction "1_1") (pintype "bidirectional"))
      (node (ref "RCOMH-1") (pin "1") (pinfunction "1_1") (pintype "passive"))
    )
    (net (code "163") (name "Net-(CCOMLN-Pad1)") (class "Default")
      (node (ref "CCOMLN") (pin "1") (pinfunction "1_1") (pintype "passive"))
      (node (ref "COMML") (pin "2") (pinfunction "2_2") (pintype "passive"))
    )
    (net (code "164") (name "Net-(CCOMLN-Pad2)") (class "Default")
      (node (ref "CCOMLN") (pin "2") (pinfunction "2_2") (pintype "passive"))
      (node (ref "D1") (pin "1") (pinfunction "1_1") (pintype "bidirectional"))
      (node (ref "RCOML1") (pin "1") (pinfunction "1_1") (pintype "passive"))
    )
    (net (code "165") (name "Net-(CCOMLP-Pad1)") (class "Default")
      (node (ref "CCOMLP") (pin "1") (pinfunction "1_1") (pintype "passive"))
      (node (ref "COMML") (pin "4") (pinfunction "4_4") (pintype "passive"))
    )
    (net (code "166") (name "Net-(CCOMLP-Pad2)") (class "Default")
      (node (ref "CCOMLP") (pin "2") (pinfunction "2_2") (pintype "passive"))
      (node (ref "D1") (pin "2") (pinfunction "2_2") (pintype "bidirectional"))
      (node (ref "RCOML") (pin "1") (pinfunction "1_1") (pintype "passive"))
    )
    (net (code "167") (name "Net-(CISOL-Pad2)") (class "Default")
      (node (ref "CISOL") (pin "2") (pinfunction "2_2") (pintype "passive"))
      (node (ref "RCOMH") (pin "1") (pinfunction "1_1") (pintype "passive"))
    )
    (net (code "168") (name "Net-(CISOL1-Pad2)") (class "Default")
      (node (ref "CISOL1") (pin "2") (pinfunction "2_2") (pintype "passive"))
      (node (ref "RCOMH1") (pin "1") (pinfunction "1_1") (pintype "passive"))
    )
    (net (code "169") (name "Net-(CNPN-1-Pad2)") (class "Default")
      (node (ref "CNPN-1") (pin "2") (pinfunction "2_2") (pintype "passive"))
      (node (ref "RNPN-1") (pin "2") (pinfunction "2_2") (pintype "passive"))
      (node (ref "T2") (pin "C") (pinfunction "C_C") (pintype "passive"))
    )
    (net (code "170") (name "Net-(CNPN-Pad2)") (class "Default")
      (node (ref "CNPN") (pin "2") (pinfunction "2_2") (pintype "passive"))
      (node (ref "RNPN") (pin "2") (pinfunction "2_2") (pintype "passive"))
      (node (ref "T1") (pin "C") (pinfunction "C_C") (pintype "passive"))
    )
    (net (code "171") (name "Net-(IC1-NEG5V)") (class "Default")
      (node (ref "CNEG5V-1") (pin "1") (pinfunction "1_1") (pintype "passive"))
      (node (ref "IC1") (pin "44") (pinfunction "NEG5V_44") (pintype "bidirectional"))
    )
    (net (code "172") (name "Net-(IC2-CB10)") (class "Default")
      (node (ref "CCB10") (pin "1") (pinfunction "1_1") (pintype "passive"))
      (node (ref "CCB11") (pin "2") (pinfunction "2_2") (pintype "passive"))
      (node (ref "IC2") (pin "14") (pinfunction "CB10_14") (pintype "bidirectional"))
      (node (ref "RCB10") (pin "2") (pinfunction "2_2") (pintype "passive"))
    )
    (net (code "173") (name "Net-(IC2-CB11)") (class "Default")
      (node (ref "CCB11") (pin "1") (pinfunction "1_1") (pintype "passive"))
      (node (ref "CCB12") (pin "2") (pinfunction "2_2") (pintype "passive"))
      (node (ref "IC2") (pin "12") (pinfunction "CB11_12") (pintype "bidirectional"))
      (node (ref "RCB11") (pin "2") (pinfunction "2_2") (pintype "passive"))
    )
    (net (code "174") (name "Net-(IC2-CB12)") (class "Default")
      (node (ref "CCB12") (pin "1") (pinfunction "1_1") (pintype "passive"))
      (node (ref "CCB13") (pin "2") (pinfunction "2_2") (pintype "passive"))
      (node (ref "IC2") (pin "10") (pinfunction "CB12_10") (pintype "bidirectional"))
      (node (ref "RCB12") (pin "2") (pinfunction "2_2") (pintype "passive"))
    )
    (net (code "175") (name "Net-(IC2-CB13)") (class "Default")
      (node (ref "CCB13") (pin "1") (pinfunction "1_1") (pintype "passive"))
      (node (ref "CCB14") (pin "2") (pinfunction "2_2") (pintype "passive"))
      (node (ref "IC2") (pin "8") (pinfunction "CB13_8") (pintype "bidirectional"))
      (node (ref "RCB13") (pin "2") (pinfunction "2_2") (pintype "passive"))
    )
    (net (code "176") (name "Net-(IC2-CB14)") (class "Default")
      (node (ref "CCB14") (pin "1") (pinfunction "1_1") (pintype "passive"))
      (node (ref "CCB15") (pin "2") (pinfunction "2_2") (pintype "passive"))
      (node (ref "IC2") (pin "6") (pinfunction "CB14_6") (pintype "bidirectional"))
      (node (ref "RCB14") (pin "2") (pinfunction "2_2") (pintype "passive"))
    )
    (net (code "177") (name "Net-(IC2-NEG5V)") (class "Default")
      (node (ref "CNEG5V") (pin "1") (pinfunction "1_1") (pintype "passive"))
      (node (ref "IC2") (pin "44") (pinfunction "NEG5V_44") (pintype "bidirectional"))
    )
    (net (code "178") (name "Net-(IC2-VC10)") (class "Default")
      (node (ref "CVC10") (pin "1") (pinfunction "1_1") (pintype "passive"))
      (node (ref "CVC11") (pin "2") (pinfunction "2_2") (pintype "passive"))
      (node (ref "IC2") (pin "15") (pinfunction "VC10_15") (pintype "bidirectional"))
      (node (ref "RVC10") (pin "2") (pinfunction "2_2") (pintype "passive"))
    )
    (net (code "179") (name "Net-(IC2-VC11)") (class "Default")
      (node (ref "CVC11") (pin "1") (pinfunction "1_1") (pintype "passive"))
      (node (ref "CVC12") (pin "2") (pinfunction "2_2") (pintype "passive"))
      (node (ref "IC2") (pin "13") (pinfunction "VC11_13") (pintype "bidirectional"))
      (node (ref "RVC11") (pin "2") (pinfunction "2_2") (pintype "passive"))
    )
    (net (code "180") (name "Net-(IC2-VC12)") (class "Default")
      (node (ref "CVC12") (pin "1") (pinfunction "1_1") (pintype "passive"))
      (node (ref "CVC13") (pin "2") (pinfunction "2_2") (pintype "passive"))
      (node (ref "IC2") (pin "11") (pinfunction "VC12_11") (pintype "bidirectional"))
      (node (ref "RVC12") (pin "2") (pinfunction "2_2") (pintype "passive"))
    )
    (net (code "181") (name "Net-(IC2-VC13)") (class "Default")
      (node (ref "CVC13") (pin "1") (pinfunction "1_1") (pintype "passive"))
      (node (ref "CVC14") (pin "2") (pinfunction "2_2") (pintype "passive"))
      (node (ref "IC2") (pin "9") (pinfunction "VC13_9") (pintype "bidirectional"))
      (node (ref "RVC13") (pin "2") (pinfunction "2_2") (pintype "passive"))
    )
    (net (code "182") (name "Net-(IC2-VC14)") (class "Default")
      (node (ref "CVC14") (pin "1") (pinfunction "1_1") (pintype "passive"))
      (node (ref "IC2") (pin "7") (pinfunction "VC14_7") (pintype "bidirectional"))
      (node (ref "RVC14") (pin "2") (pinfunction "2_2") (pintype "passive"))
    )
    (net (code "183") (name "unconnected-(COMMH-Pad1)") (class "Default")
      (node (ref "COMMH") (pin "1") (pinfunction "1_1") (pintype "passive"))
    )
    (net (code "184") (name "unconnected-(COMMH-Pad3)") (class "Default")
      (node (ref "COMMH") (pin "3") (pinfunction "3_3") (pintype "passive"))
    )
    (net (code "185") (name "unconnected-(COMML-Pad1)") (class "Default")
      (node (ref "COMML") (pin "1") (pinfunction "1_1") (pintype "passive"))
    )
    (net (code "186") (name "unconnected-(COMML-Pad3)") (class "Default")
      (node (ref "COMML") (pin "3") (pinfunction "3_3") (pintype "passive"))
    )
    (net (code "187") (name "unconnected-(IC1-BBN(SRN)-Pad63)") (class "Default")
      (node (ref "IC1") (pin "63") (pinfunction "BBN(SRN)_63") (pintype "bidirectional"))
    )
    (net (code "188") (name "unconnected-(IC1-BBP(SRP)-Pad64)") (class "Default")
      (node (ref "IC1") (pin "64") (pinfunction "BBP(SRP)_64") (pintype "bidirectional"))
    )
    (net (code "189") (name "unconnected-(IC1-TX-Pad53)") (class "Default")
      (node (ref "IC1") (pin "53") (pinfunction "TX_53") (pintype "bidirectional"))
    )
    (net (code "190") (name "unconnected-(IC2-TX-Pad53)") (class "Default")
      (node (ref "IC2") (pin "53") (pinfunction "TX_53") (pintype "bidirectional"))
    )
    (net (code "191") (name "unconnected-(SR-Pad1)") (class "Default")
      (node (ref "SR") (pin "1") (pinfunction "1_1") (pintype "passive"))
    )
    (net (code "192") (name "unconnected-(SR-Pad2)") (class "Default")
      (node (ref "SR") (pin "2") (pinfunction "2_2") (pintype "passive"))
    )
  )
)
